# EEZ_DIB_DCP405_r2B8.net
KiCad netlist of a schematic drawn in EAGLE
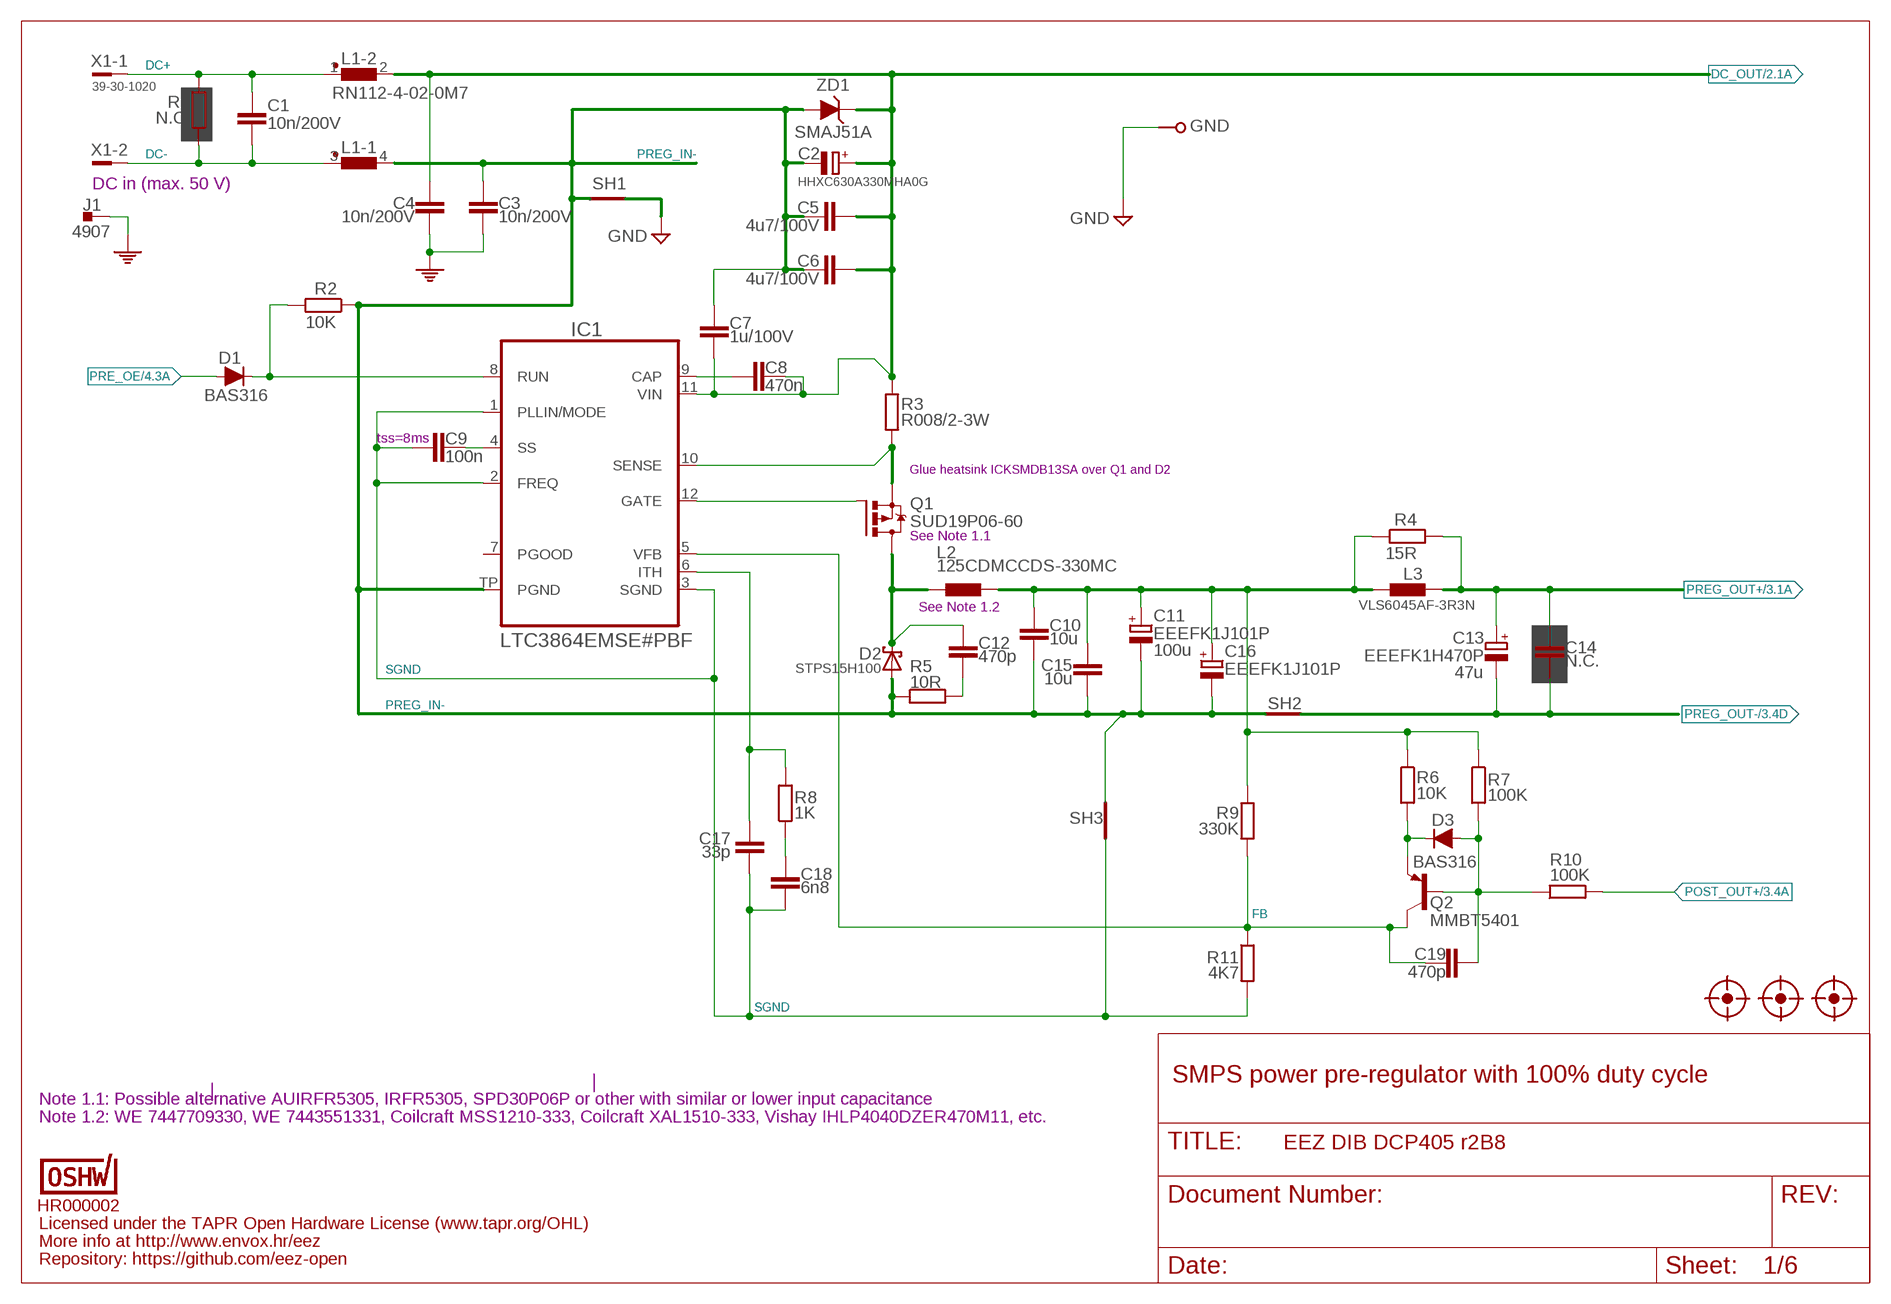
[diagram p0: schematic, sheet 1]
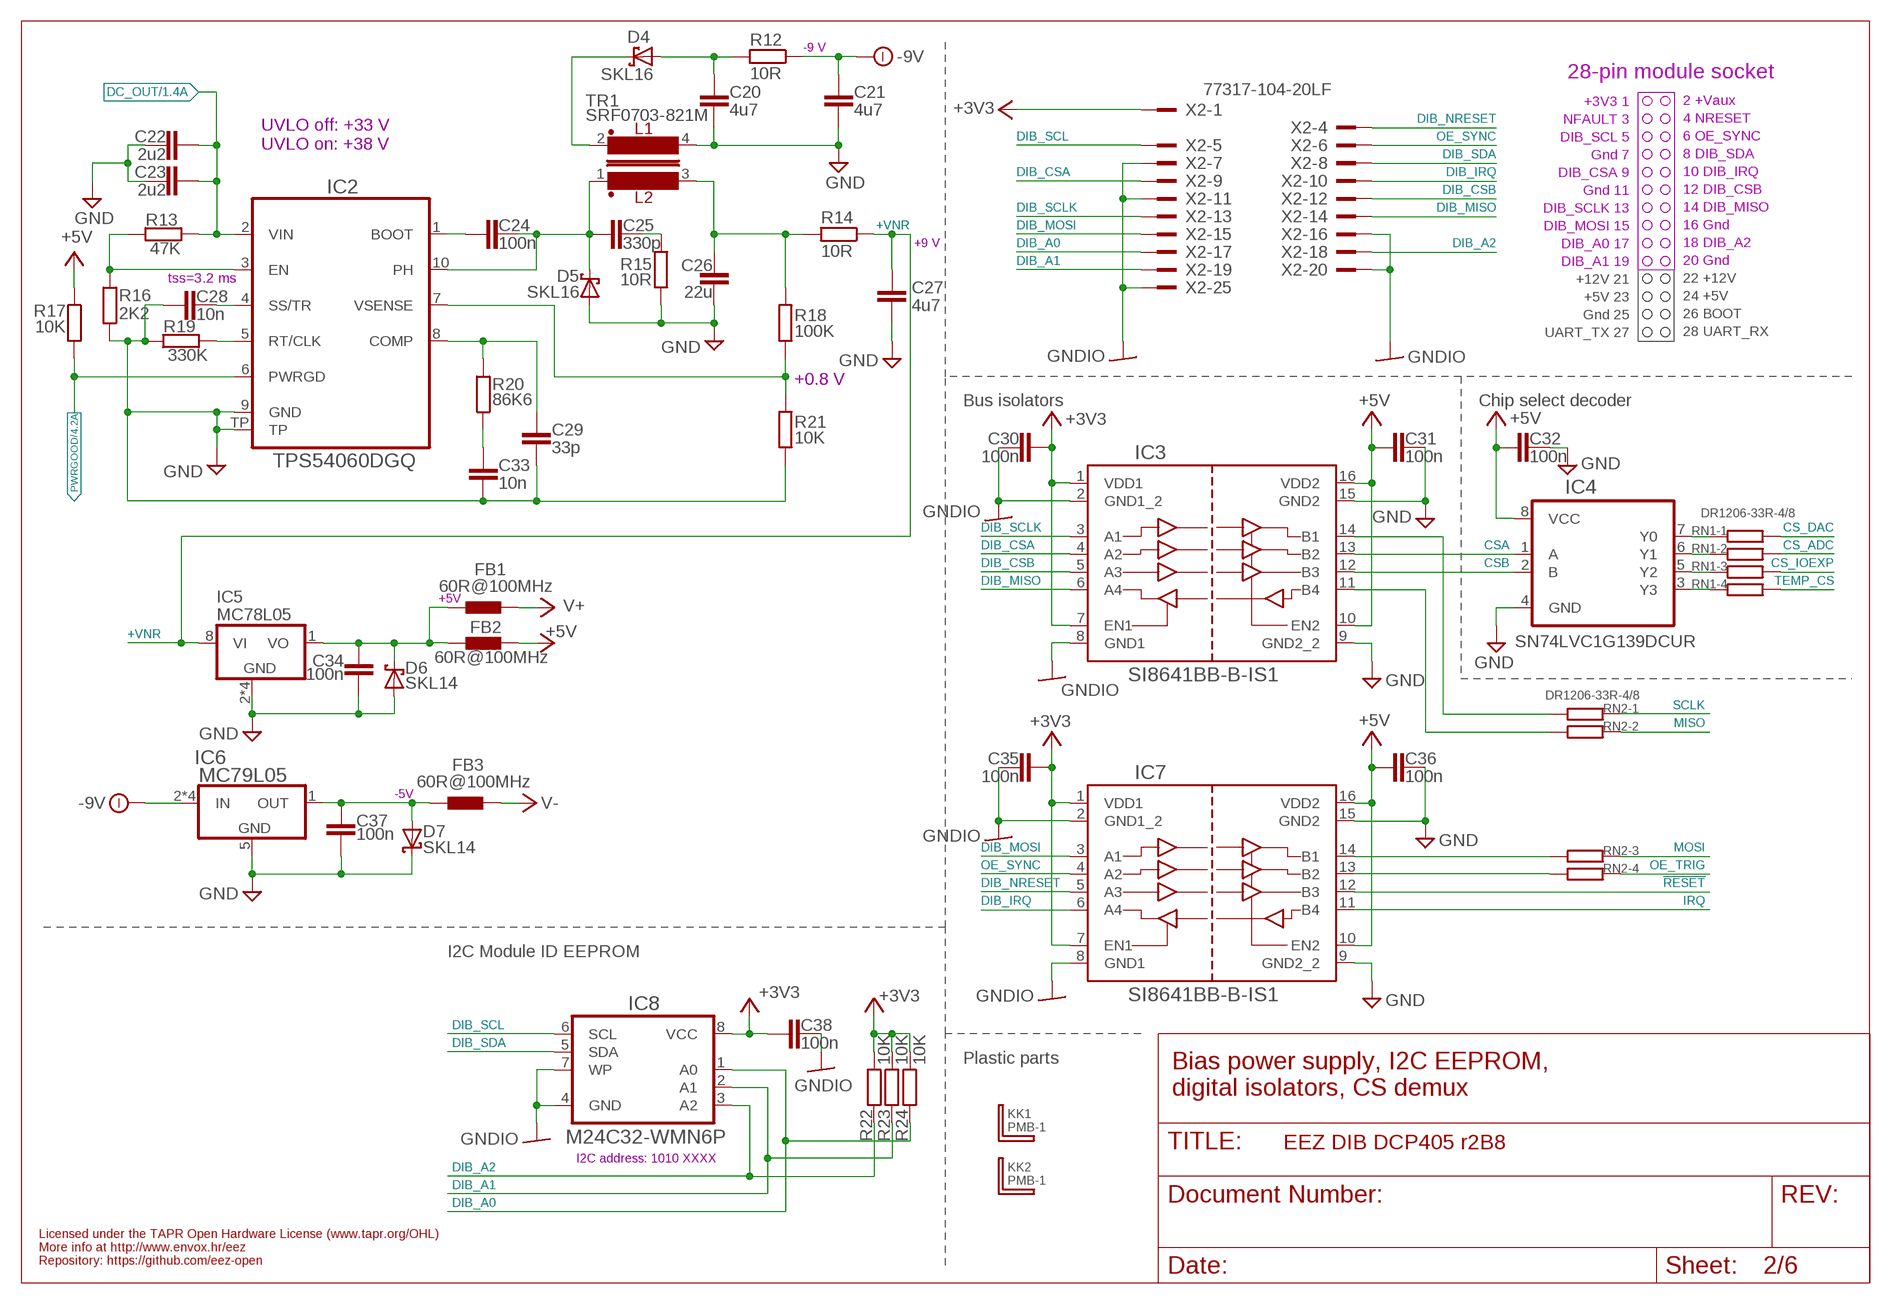
[diagram p1: schematic, sheet 2]
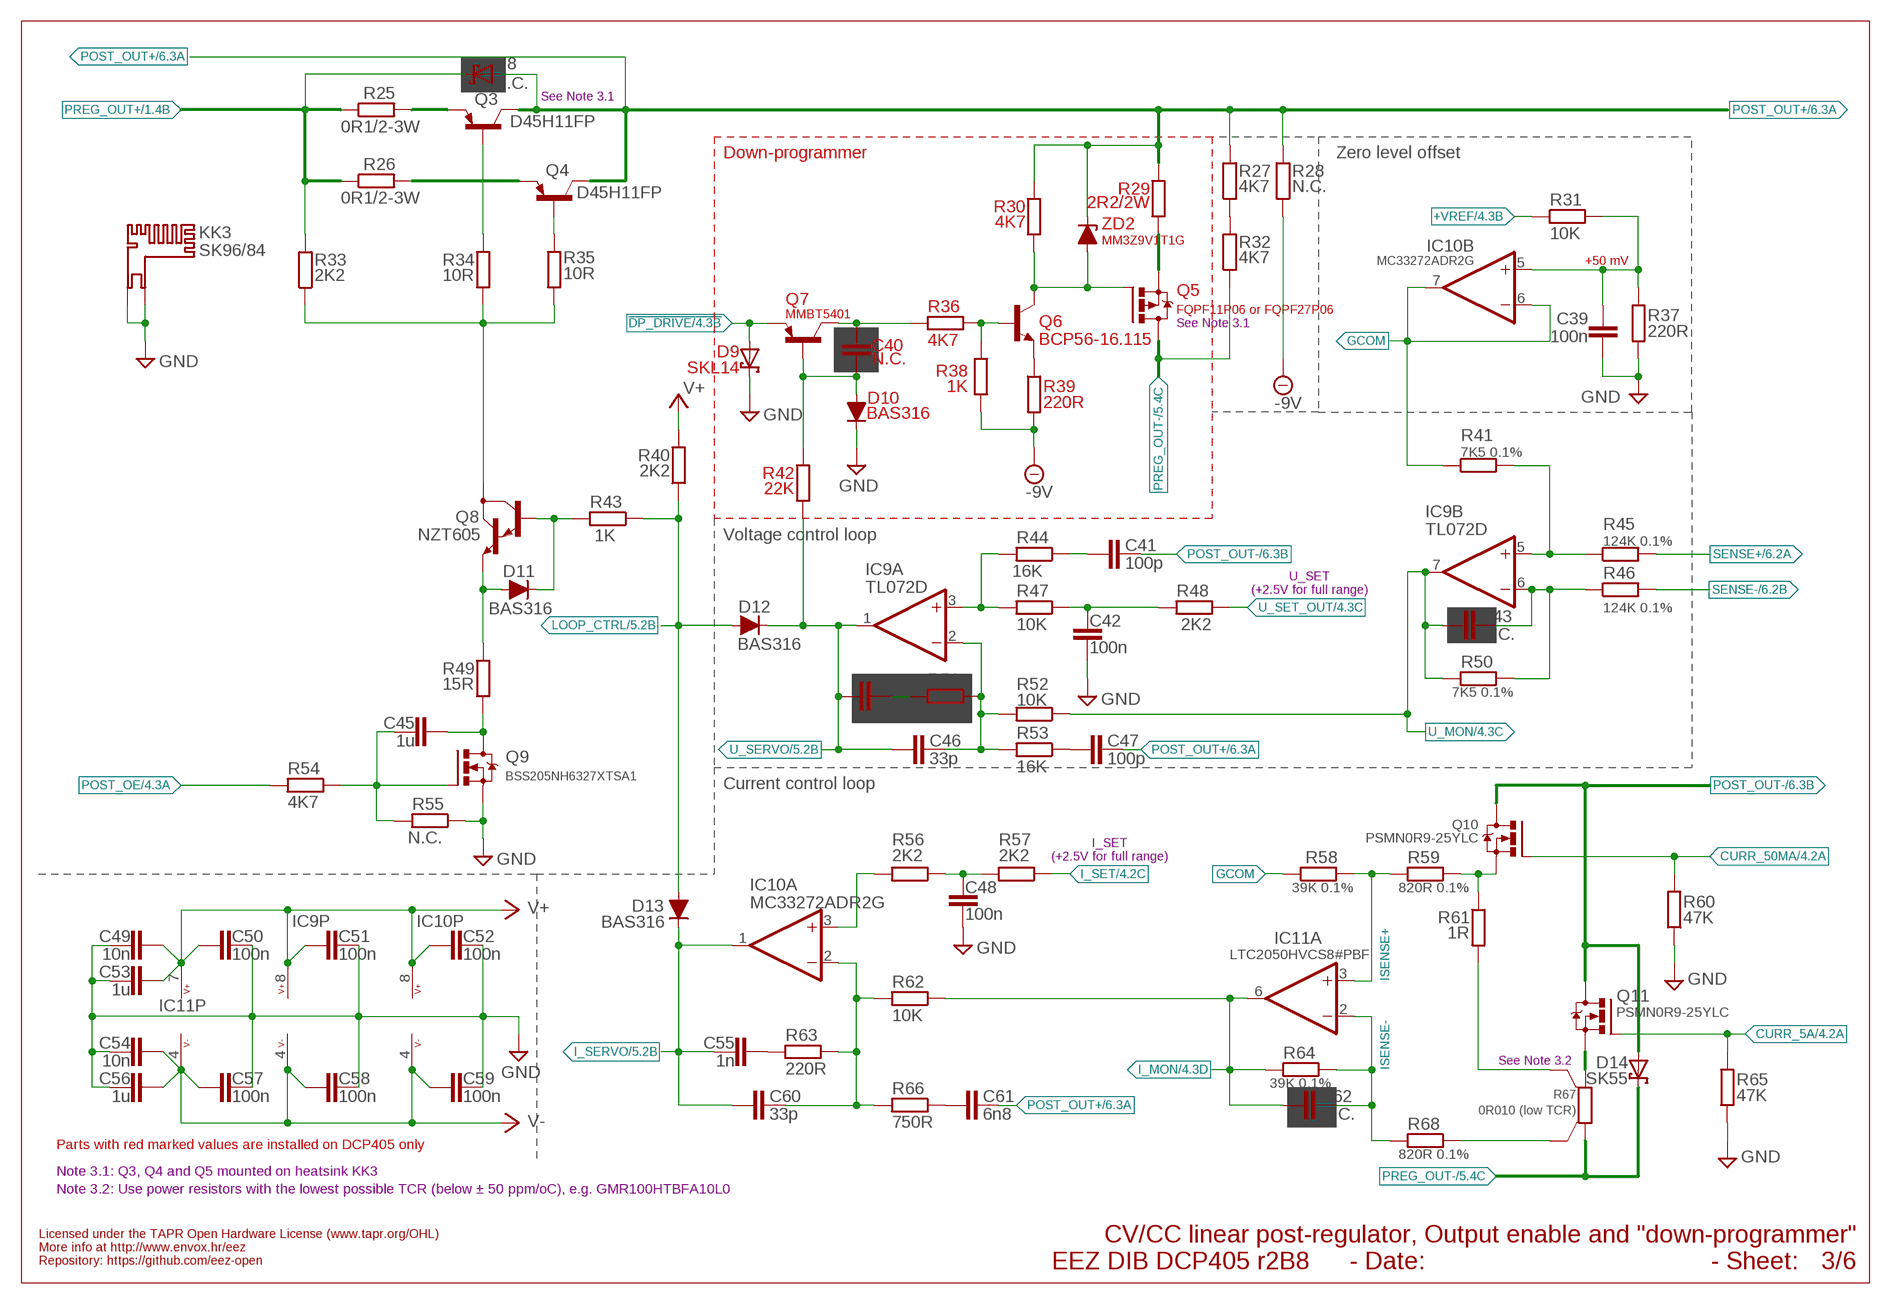
[diagram p2: schematic, sheet 3]
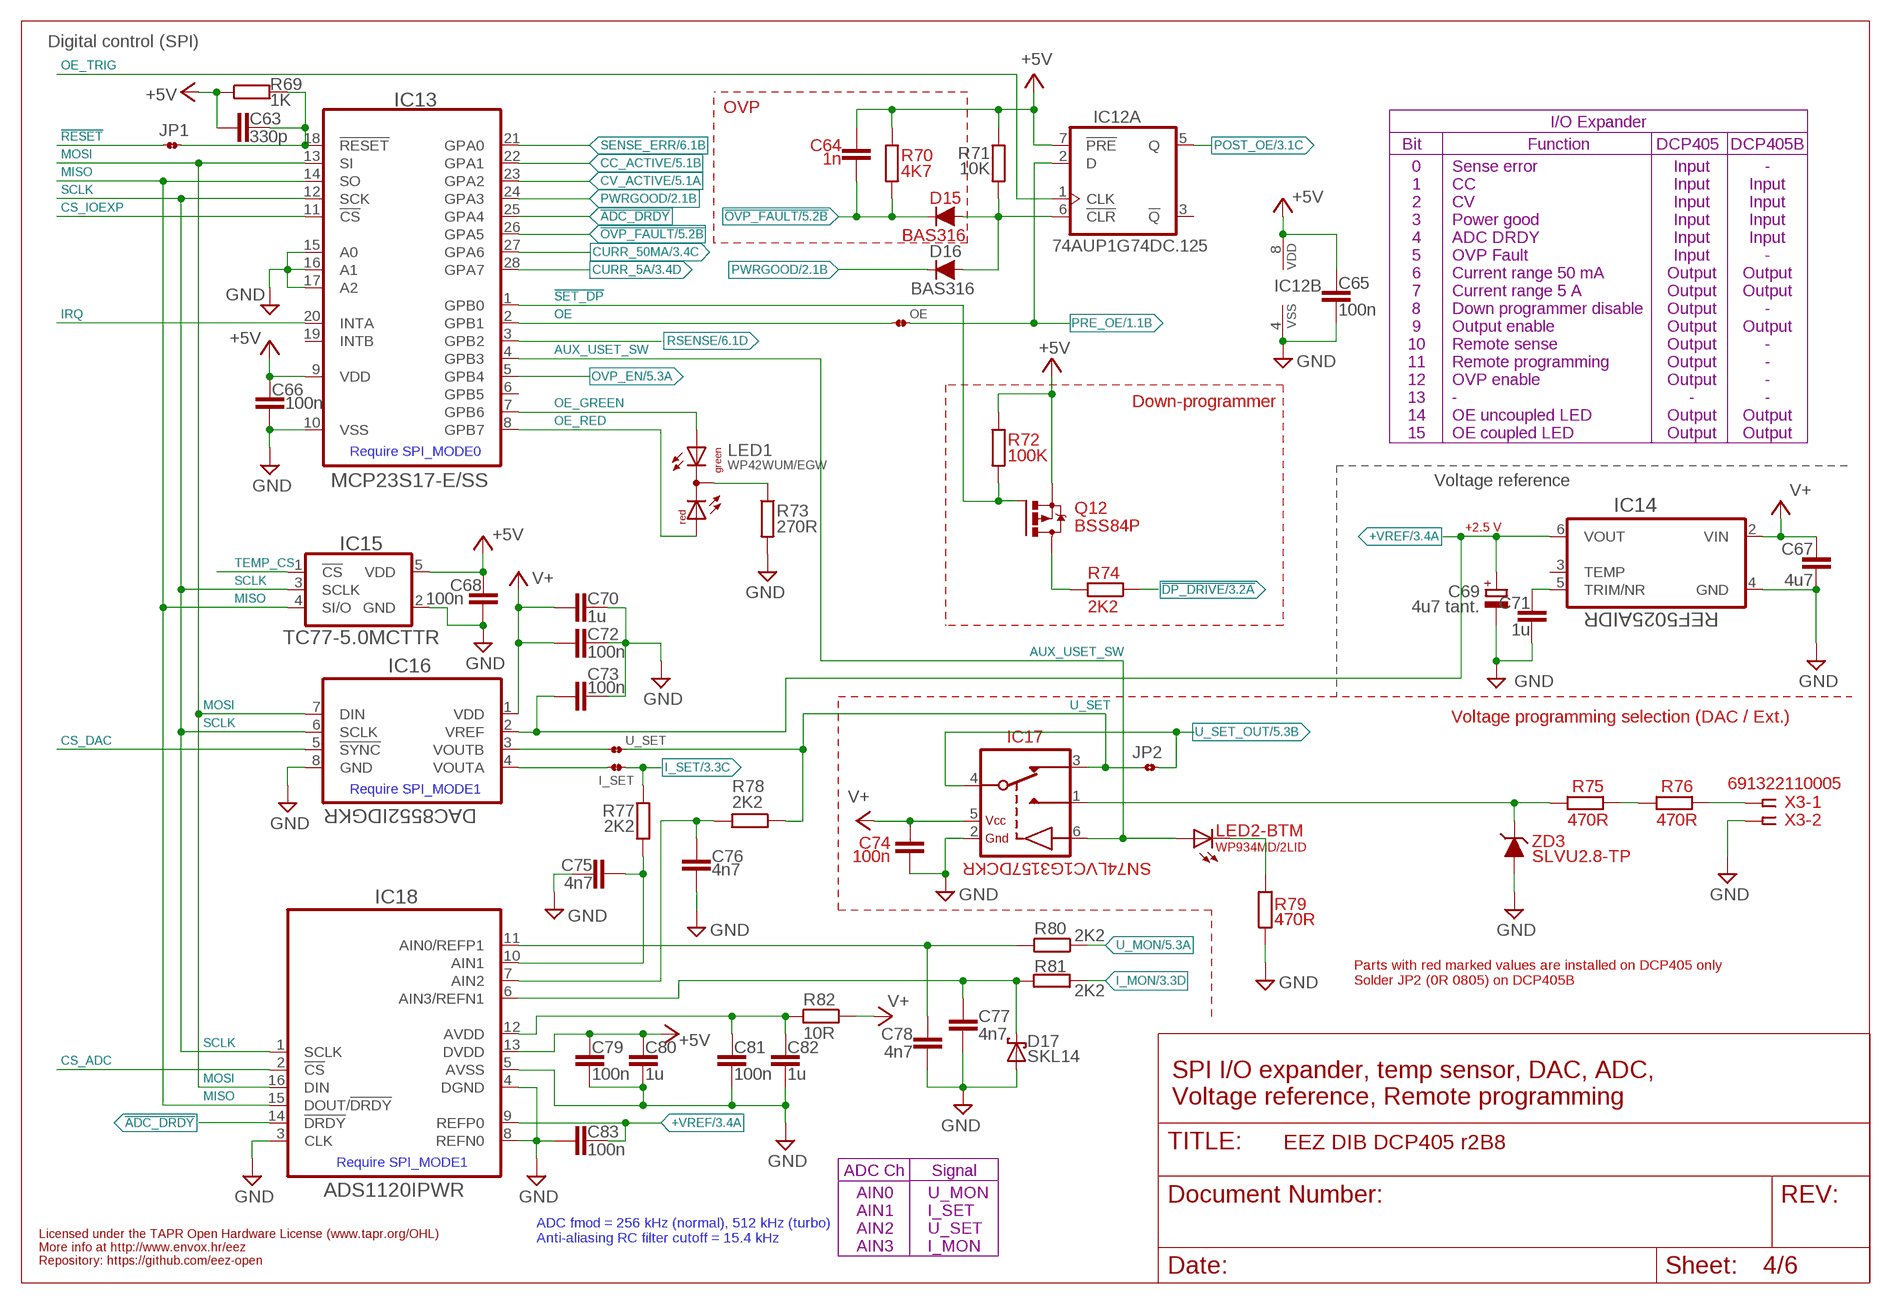
[diagram p3: schematic, sheet 4]
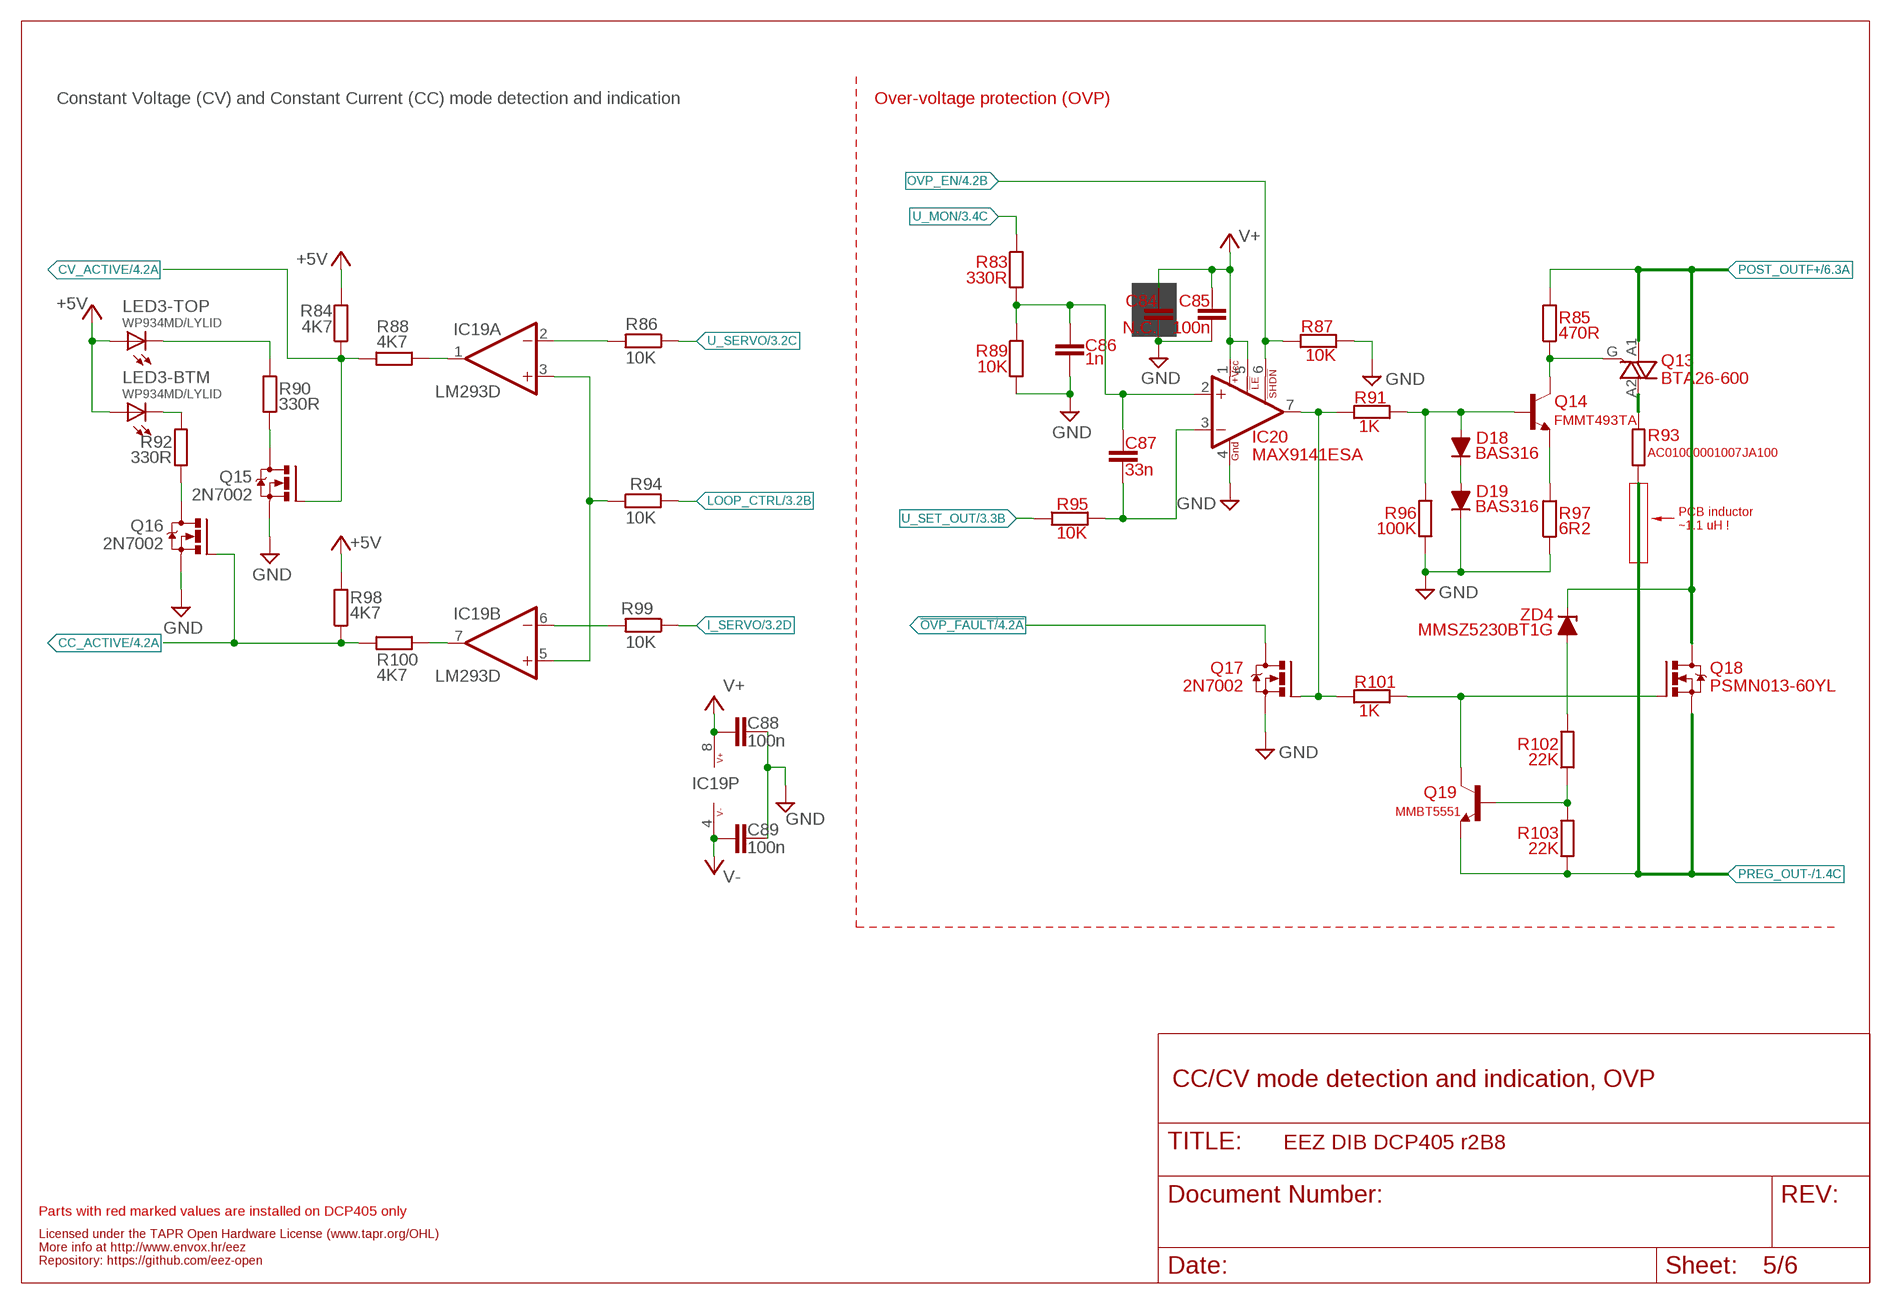
[diagram p4: schematic, sheet 5]
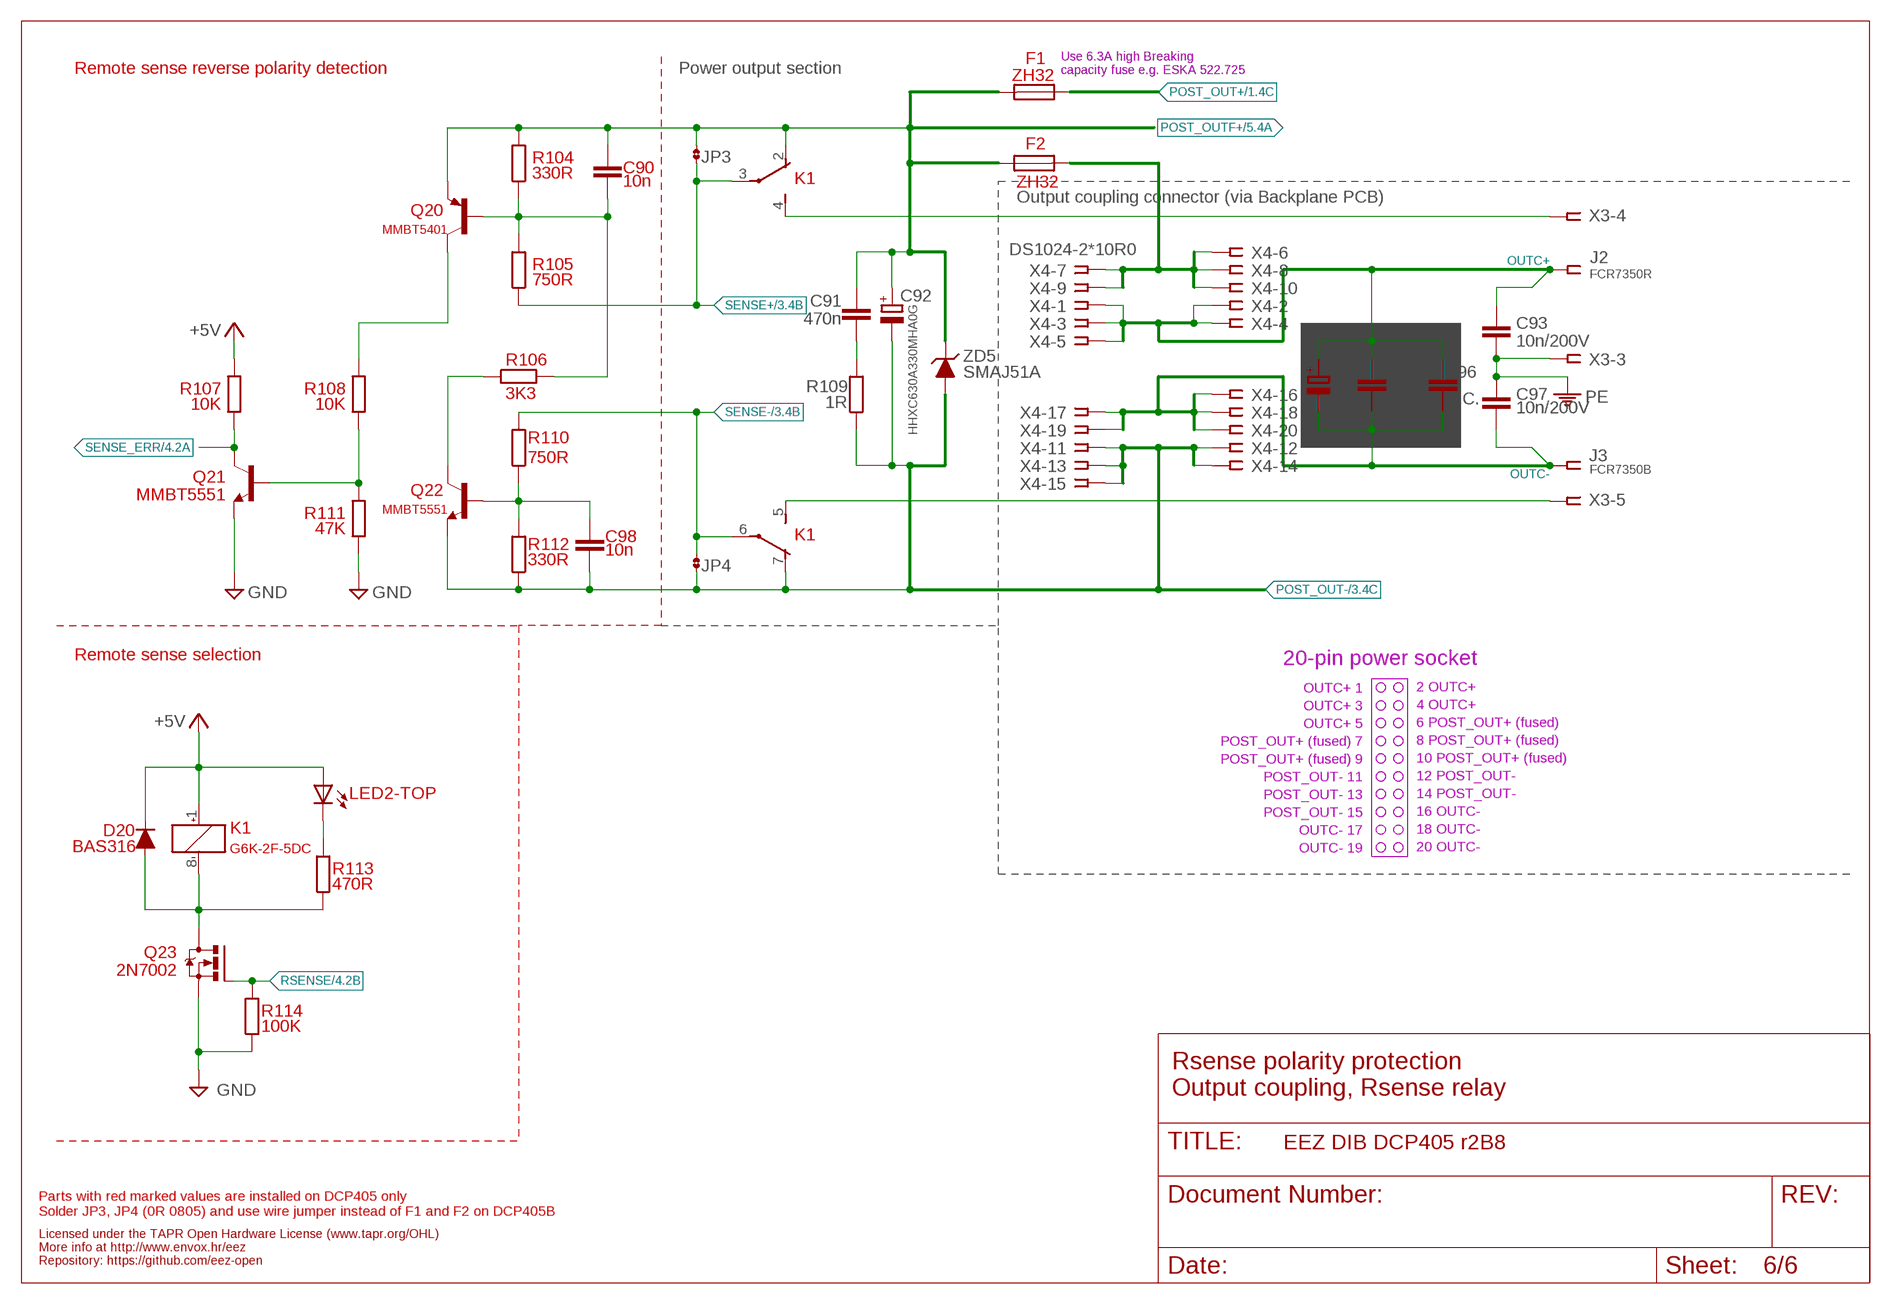
[diagram p5: schematic, sheet 6]

(export (version "E")
  (design (tool "Eeschema 10.0.6"))
  (components
    (comp (ref "C1")
      (value "10n/200V")
      (footprint "eagle-import:C1206")
      (libsource (lib "eagle-import") (part "C-EUC1206"))
    )
    (comp (ref "C2")
      (value "HHXC630A330MHA0G")
      (footprint "eagle-import:CAPAE830X1050N")
      (libsource (lib "eagle-import") (part "ECAPSMD8.3MM/HA0"))
    )
    (comp (ref "C3")
      (value "10n/200V")
      (footprint "eagle-import:C1206")
      (libsource (lib "eagle-import") (part "C-EUC1206"))
    )
    (comp (ref "C4")
      (value "10n/200V")
      (footprint "eagle-import:C1206")
      (libsource (lib "eagle-import") (part "C-EUC1206"))
    )
    (comp (ref "C5")
      (value "4u7/100V")
      (footprint "eagle-import:C1210")
      (libsource (lib "eagle-import") (part "C-EUC1210"))
    )
    (comp (ref "C6")
      (value "4u7/100V")
      (footprint "eagle-import:C1210")
      (libsource (lib "eagle-import") (part "C-EUC1210"))
    )
    (comp (ref "C7")
      (value "1u/100V")
      (footprint "eagle-import:C1206")
      (libsource (lib "eagle-import") (part "C-EUC1206"))
    )
    (comp (ref "C8")
      (value "470n")
      (footprint "eagle-import:C0805")
      (libsource (lib "eagle-import") (part "C-EUC0805"))
    )
    (comp (ref "C9")
      (value "100n")
      (footprint "eagle-import:C0603")
      (libsource (lib "eagle-import") (part "C-EUC0603"))
    )
    (comp (ref "C10")
      (value "10u")
      (footprint "eagle-import:C1210")
      (libsource (lib "eagle-import") (part "C-EUC1210"))
    )
    (comp (ref "C11")
      (value "EEEFK1J101P")
      (footprint "eagle-import:CAPAE1030X1050N")
      (libsource (lib "eagle-import") (part "ECAP10X10"))
    )
    (comp (ref "C12")
      (value "470p")
      (footprint "eagle-import:C0805")
      (libsource (lib "eagle-import") (part "C-EUC0805"))
    )
    (comp (ref "C13")
      (value "EEEFK1H470P")
      (footprint "eagle-import:CAPAE830X1050N")
      (libsource (lib "eagle-import") (part "ECAPSMD8.3MM/HA0"))
    )
    (comp (ref "C14")
      (value "N.C.")
      (footprint "eagle-import:C0805")
      (libsource (lib "eagle-import") (part "C-EUC0805"))
    )
    (comp (ref "C15")
      (value "10u")
      (footprint "eagle-import:C1210")
      (libsource (lib "eagle-import") (part "C-EUC1210"))
    )
    (comp (ref "C16")
      (value "EEEFK1J101P")
      (footprint "eagle-import:CAPAE1030X1050N")
      (libsource (lib "eagle-import") (part "ECAP10X10"))
    )
    (comp (ref "C17")
      (value "33p")
      (footprint "eagle-import:C0805")
      (libsource (lib "eagle-import") (part "C-EUC0805"))
    )
    (comp (ref "C18")
      (value "6n8")
      (footprint "eagle-import:C0805")
      (libsource (lib "eagle-import") (part "C-EUC0805"))
    )
    (comp (ref "C19")
      (value "470p")
      (footprint "eagle-import:C0805")
      (libsource (lib "eagle-import") (part "C-EUC0805"))
    )
    (comp (ref "D1")
      (value "BAS316")
      (footprint "eagle-import:SOD323-R")
      (libsource (lib "eagle-import") (part "DIODESOD323R"))
    )
    (comp (ref "D2")
      (value "STPS15H100")
      (footprint "eagle-import:TO252-L")
      (libsource (lib "eagle-import") (part "SCHOTTKY-DUAL_A_L"))
    )
    (comp (ref "D3")
      (value "BAS316")
      (footprint "eagle-import:SOD323-R")
      (libsource (lib "eagle-import") (part "DIODESOD323R"))
    )
    (comp (ref "FM1")
      (value "FIDUCIAL_2")
      (footprint "eagle-import:FIDUCIAL_DUAL")
      (libsource (lib "eagle-import") (part "FIDUCIAL_2"))
    )
    (comp (ref "FM2")
      (value "FIDUCIAL_2")
      (footprint "eagle-import:FIDUCIAL_DUAL")
      (libsource (lib "eagle-import") (part "FIDUCIAL_2"))
    )
    (comp (ref "FM3")
      (value "FIDUCIAL_2")
      (footprint "eagle-import:FIDUCIAL_DUAL")
      (libsource (lib "eagle-import") (part "FIDUCIAL_2"))
    )
    (comp (ref "GND")
      (value "PCB_TEST_TABSHIELD")
      (footprint "eagle-import:PCB_SHIELD_TAB")
      (libsource (lib "eagle-import") (part "PCB_TEST_TABSHIELD"))
    )
    (comp (ref "IC1")
      (value "LTC3864EMSE#PBF")
      (footprint "eagle-import:LTC_05-08-1666")
      (libsource (lib "eagle-import") (part "LTC3864"))
    )
    (comp (ref "J1")
      (value "4907")
      (footprint "eagle-import:PCB_TAB-4907")
      (libsource (lib "eagle-import") (part "PCB_TAB-4907"))
    )
    (comp (ref "L1")
      (value "RN112-4-02-0M7")
      (footprint "eagle-import:RN112")
      (libsource (lib "eagle-import") (part "RN112"))
    )
    (comp (ref "L2")
      (value "125CDMCCDS-330MC")
      (footprint "eagle-import:125CDMCC_DS")
      (libsource (lib "eagle-import") (part "125CDMCC/DS"))
    )
    (comp (ref "L3")
      (value "VLS6045AF-3R3N")
      (footprint "eagle-import:COILCRAFT_HPI0630")
      (libsource (lib "eagle-import") (part "COILCRAFT_HPI0630"))
    )
    (comp (ref "OSHWA")
      (value "HR000002")
      (footprint "eagle-import:CERT-SMALL-SILK")
      (libsource (lib "eagle-import") (part "OSHWA-CERT-SMALL"))
    )
    (comp (ref "Q1")
      (value "SUD19P06-60")
      (footprint "eagle-import:TO229P990X239-3N")
      (libsource (lib "eagle-import") (part "P-MOSFETDPAK"))
    )
    (comp (ref "Q2")
      (value "MMBT5401")
      (footprint "eagle-import:SOT23-BEC")
      (libsource (lib "eagle-import") (part "-PNP-SOT23-BECBC857B"))
    )
    (comp (ref "R1")
      (value "N.C.")
      (footprint "eagle-import:R2512")
      (libsource (lib "eagle-import") (part "R-EU_R2512"))
    )
    (comp (ref "R2")
      (value "10K")
      (footprint "eagle-import:R0805")
      (libsource (lib "eagle-import") (part "R-EU_R0805"))
    )
    (comp (ref "R3")
      (value "R008/2-3W")
      (footprint "eagle-import:R2512")
      (libsource (lib "eagle-import") (part "R-EU_R2512"))
    )
    (comp (ref "R4")
      (value "15R")
      (footprint "eagle-import:R2010")
      (libsource (lib "eagle-import") (part "R-EU_R2010"))
    )
    (comp (ref "R5")
      (value "10R")
      (footprint "eagle-import:R1206")
      (libsource (lib "eagle-import") (part "R-EU_R1206"))
    )
    (comp (ref "R6")
      (value "10K")
      (footprint "eagle-import:R0805")
      (libsource (lib "eagle-import") (part "R-EU_R0805"))
    )
    (comp (ref "R7")
      (value "100K")
      (footprint "eagle-import:R0805")
      (libsource (lib "eagle-import") (part "R-EU_R0805"))
    )
    (comp (ref "R8")
      (value "1K")
      (footprint "eagle-import:R0805")
      (libsource (lib "eagle-import") (part "R-EU_R0805"))
    )
    (comp (ref "R9")
      (value "330K")
      (footprint "eagle-import:R0805")
      (libsource (lib "eagle-import") (part "R-EU_R0805"))
    )
    (comp (ref "R10")
      (value "100K")
      (footprint "eagle-import:R0805")
      (libsource (lib "eagle-import") (part "R-EU_R0805"))
    )
    (comp (ref "R11")
      (value "4K7")
      (footprint "eagle-import:R0805")
      (libsource (lib "eagle-import") (part "R-EU_R0805"))
    )
    (comp (ref "SH1")
      (value "SHORTNOHOLE")
      (footprint "eagle-import:SHORT_NOHOLE")
      (libsource (lib "eagle-import") (part "SHORTNOHOLE"))
    )
    (comp (ref "SH2")
      (value "Pgnd to Pout- short")
      (footprint "eagle-import:SHORT_NOHOLE")
      (libsource (lib "eagle-import") (part "SHORTNOHOLE"))
    )
    (comp (ref "SH3")
      (value "Sgnd to Pgnd short")
      (footprint "eagle-import:SHORT_NOHOLE")
      (libsource (lib "eagle-import") (part "SHORTNOHOLE"))
    )
    (comp (ref "X1")
      (value "39-30-1020")
      (footprint "eagle-import:MINIFIT_39301020")
      (libsource (lib "eagle-import") (part "MINIFIT_39301020"))
    )
    (comp (ref "ZD1")
      (value "SMAJ51A")
      (footprint "eagle-import:DO214AA")
      (libsource (lib "eagle-import") (part "P6SMB68A"))
    )
    (comp (ref "C63")
      (value "330p")
      (footprint "eagle-import:C0805")
      (libsource (lib "eagle-import") (part "C-EUC0805"))
    )
    (comp (ref "C64")
      (value "1n")
      (footprint "eagle-import:C0805")
      (libsource (lib "eagle-import") (part "C-EUC0805"))
    )
    (comp (ref "C65")
      (value "100n")
      (footprint "eagle-import:C0603")
      (libsource (lib "eagle-import") (part "C-EUC0603"))
    )
    (comp (ref "C66")
      (value "100n")
      (footprint "eagle-import:C0603")
      (libsource (lib "eagle-import") (part "C-EUC0603"))
    )
    (comp (ref "C67")
      (value "4u7")
      (footprint "eagle-import:C1206")
      (libsource (lib "eagle-import") (part "C-EUC1206"))
    )
    (comp (ref "C68")
      (value "100n")
      (footprint "eagle-import:C0603")
      (libsource (lib "eagle-import") (part "C-EUC0603"))
    )
    (comp (ref "C69")
      (value "4u7 tant.")
      (footprint "eagle-import:EC1206")
      (libsource (lib "eagle-import") (part "ECAP1206"))
    )
    (comp (ref "C70")
      (value "1u")
      (footprint "eagle-import:C0805")
      (libsource (lib "eagle-import") (part "C-EUC0805"))
    )
    (comp (ref "C71")
      (value "1u")
      (footprint "eagle-import:C0805")
      (libsource (lib "eagle-import") (part "C-EUC0805"))
    )
    (comp (ref "C72")
      (value "100n")
      (footprint "eagle-import:C0603")
      (libsource (lib "eagle-import") (part "C-EUC0603"))
    )
    (comp (ref "C73")
      (value "100n")
      (footprint "eagle-import:C0603")
      (libsource (lib "eagle-import") (part "C-EUC0603"))
    )
    (comp (ref "C74")
      (value "100n")
      (footprint "eagle-import:C0603")
      (libsource (lib "eagle-import") (part "C-EUC0603"))
    )
    (comp (ref "C75")
      (value "4n7")
      (footprint "eagle-import:C0805")
      (libsource (lib "eagle-import") (part "C-EUC0805"))
    )
    (comp (ref "C76")
      (value "4n7")
      (footprint "eagle-import:C0805")
      (libsource (lib "eagle-import") (part "C-EUC0805"))
    )
    (comp (ref "C77")
      (value "4n7")
      (footprint "eagle-import:C0805")
      (libsource (lib "eagle-import") (part "C-EUC0805"))
    )
    (comp (ref "C78")
      (value "4n7")
      (footprint "eagle-import:C0805")
      (libsource (lib "eagle-import") (part "C-EUC0805"))
    )
    (comp (ref "C79")
      (value "100n")
      (footprint "eagle-import:C0603")
      (libsource (lib "eagle-import") (part "C-EUC0603"))
    )
    (comp (ref "C80")
      (value "1u")
      (footprint "eagle-import:C0805")
      (libsource (lib "eagle-import") (part "C-EUC0805"))
    )
    (comp (ref "C81")
      (value "100n")
      (footprint "eagle-import:C0603")
      (libsource (lib "eagle-import") (part "C-EUC0603"))
    )
    (comp (ref "C82")
      (value "1u")
      (footprint "eagle-import:C0805")
      (libsource (lib "eagle-import") (part "C-EUC0805"))
    )
    (comp (ref "C83")
      (value "100n")
      (footprint "eagle-import:C0603")
      (libsource (lib "eagle-import") (part "C-EUC0603"))
    )
    (comp (ref "D15")
      (value "BAS316")
      (footprint "eagle-import:SOD323-R")
      (libsource (lib "eagle-import") (part "DIODESOD323R"))
    )
    (comp (ref "D16")
      (value "BAS316")
      (footprint "eagle-import:SOD323-R")
      (libsource (lib "eagle-import") (part "DIODESOD323R"))
    )
    (comp (ref "D17")
      (value "SKL14")
      (footprint "eagle-import:SOD123")
      (libsource (lib "eagle-import") (part "SCHOTTKYSOD123"))
    )
    (comp (ref "IC12")
      (value "74AUP1G74DC.125")
      (footprint "eagle-import:DCU8")
      (libsource (lib "eagle-import") (part "SN74LVC1G74DCTR-VSSOP"))
    )
    (comp (ref "IC13")
      (value "MCP23S17-E/SS")
      (footprint "eagle-import:SOP65P780X200-28N")
      (libsource (lib "eagle-import") (part "MCP23S17-E/SSSSOP"))
    )
    (comp (ref "IC14")
      (value "REF5025AIDR")
      (footprint "eagle-import:SOIC127P600X175-8N")
      (libsource (lib "eagle-import") (part "REF50XX"))
    )
    (comp (ref "IC15")
      (value "TC77-5.0MCTTR")
      (footprint "eagle-import:SOT23-5")
      (libsource (lib "eagle-import") (part "TC77"))
    )
    (comp (ref "IC16")
      (value "DAC8552IDGKR")
      (footprint "eagle-import:DGK8-M")
      (libsource (lib "eagle-import") (part "DAC8552_DGK_8M"))
    )
    (comp (ref "IC17")
      (value "SN74LVC1G3157DCKR")
      (footprint "eagle-import:SOT65P210X110-6N")
      (libsource (lib "eagle-import") (part "SN74LVC1G3157-DCK"))
    )
    (comp (ref "IC18")
      (value "ADS1120IPWR")
      (footprint "eagle-import:PW(R-PDSO-G16)")
      (libsource (lib "eagle-import") (part "ADS1120TSSOP-16"))
    )
    (comp (ref "I_SET")
      (value "JP2-NOCUT")
      (footprint "eagle-import:JP2-NOCUT")
      (libsource (lib "eagle-import") (part "JP2-NOCUT"))
    )
    (comp (ref "JP1")
      (value "JP2-NOCUT")
      (footprint "eagle-import:JP2-NOCUT")
      (libsource (lib "eagle-import") (part "JP2-NOCUT"))
    )
    (comp (ref "JP2")
      (value "JP2-CUT-0805")
      (footprint "eagle-import:R_0805")
      (libsource (lib "eagle-import") (part "JP2-CUT-0805"))
    )
    (comp (ref "LED1")
      (value "WP42WUM/EGW")
      (footprint "eagle-import:L-42WUM-1EGWT")
      (libsource (lib "eagle-import") (part "LED_L-42WUM/1EGWT"))
    )
    (comp (ref "LED2")
      (value "WP934MD/2LID")
      (footprint "eagle-import:WP934MD")
      (libsource (lib "eagle-import") (part "WP934MD/2LID"))
    )
    (comp (ref "OE")
      (value "JP2-NOCUT")
      (footprint "eagle-import:JP2-NOCUT")
      (libsource (lib "eagle-import") (part "JP2-NOCUT"))
    )
    (comp (ref "Q12")
      (value "BSS84P")
      (footprint "eagle-import:SOT95P237X112-3N")
      (fields (field (name "MPN") "IRLML2246TRPBF"))
      (libsource (lib "eagle-import") (part "IRLML2246TRPBF"))
    )
    (comp (ref "R69")
      (value "1K")
      (footprint "eagle-import:R0805")
      (libsource (lib "eagle-import") (part "R-EU_R0805"))
    )
    (comp (ref "R70")
      (value "4K7")
      (footprint "eagle-import:R0805")
      (libsource (lib "eagle-import") (part "R-EU_R0805"))
    )
    (comp (ref "R71")
      (value "10K")
      (footprint "eagle-import:R0805")
      (libsource (lib "eagle-import") (part "R-EU_R0805"))
    )
    (comp (ref "R72")
      (value "100K")
      (footprint "eagle-import:R0805")
      (libsource (lib "eagle-import") (part "R-EU_R0805"))
    )
    (comp (ref "R73")
      (value "270R")
      (footprint "eagle-import:R0805")
      (libsource (lib "eagle-import") (part "R-EU_R0805"))
    )
    (comp (ref "R74")
      (value "2K2")
      (footprint "eagle-import:R0805")
      (libsource (lib "eagle-import") (part "R-EU_R0805"))
    )
    (comp (ref "R75")
      (value "470R")
      (footprint "eagle-import:R0805")
      (libsource (lib "eagle-import") (part "R-EU_R0805"))
    )
    (comp (ref "R76")
      (value "470R")
      (footprint "eagle-import:R0805")
      (libsource (lib "eagle-import") (part "R-EU_R0805"))
    )
    (comp (ref "R77")
      (value "2K2")
      (footprint "eagle-import:R0805")
      (libsource (lib "eagle-import") (part "R-EU_R0805"))
    )
    (comp (ref "R78")
      (value "2K2")
      (footprint "eagle-import:R0805")
      (libsource (lib "eagle-import") (part "R-EU_R0805"))
    )
    (comp (ref "R79")
      (value "470R")
      (footprint "eagle-import:R0805")
      (libsource (lib "eagle-import") (part "R-EU_R0805"))
    )
    (comp (ref "R80")
      (value "2K2")
      (footprint "eagle-import:R0805")
      (libsource (lib "eagle-import") (part "R-EU_R0805"))
    )
    (comp (ref "R81")
      (value "2K2")
      (footprint "eagle-import:R0805")
      (libsource (lib "eagle-import") (part "R-EU_R0805"))
    )
    (comp (ref "R82")
      (value "10R")
      (footprint "eagle-import:R1206")
      (libsource (lib "eagle-import") (part "R-EU_R1206"))
    )
    (comp (ref "U_SET")
      (value "JP2-NOCUT")
      (footprint "eagle-import:JP2-NOCUT")
      (libsource (lib "eagle-import") (part "JP2-NOCUT"))
    )
    (comp (ref "X3")
      (value "691322110005")
      (footprint "eagle-import:MC1,5_5-G-3,5")
      (libsource (lib "eagle-import") (part "MC1,5/5-G-3,5"))
    )
    (comp (ref "ZD3")
      (value "SLVU2.8-TP")
      (footprint "eagle-import:SOT23")
      (libsource (lib "eagle-import") (part "SLVU2.8"))
    )
    (comp (ref "C84")
      (value "N.C.")
      (footprint "eagle-import:C0805")
      (libsource (lib "eagle-import") (part "C-EUC0805"))
    )
    (comp (ref "C85")
      (value "100n")
      (footprint "eagle-import:C0603")
      (libsource (lib "eagle-import") (part "C-EUC0603"))
    )
    (comp (ref "C86")
      (value "1n")
      (footprint "eagle-import:C0805")
      (libsource (lib "eagle-import") (part "C-EUC0805"))
    )
    (comp (ref "C87")
      (value "33n")
      (footprint "eagle-import:C0805")
      (libsource (lib "eagle-import") (part "C-EUC0805"))
    )
    (comp (ref "C88")
      (value "100n")
      (footprint "eagle-import:C0603")
      (libsource (lib "eagle-import") (part "C-EUC0603"))
    )
    (comp (ref "C89")
      (value "100n")
      (footprint "eagle-import:C0603")
      (libsource (lib "eagle-import") (part "C-EUC0603"))
    )
    (comp (ref "D18")
      (value "BAS316")
      (footprint "eagle-import:SOD323-R")
      (libsource (lib "eagle-import") (part "DIODESOD323R"))
    )
    (comp (ref "D19")
      (value "BAS316")
      (footprint "eagle-import:SOD323-R")
      (libsource (lib "eagle-import") (part "DIODESOD323R"))
    )
    (comp (ref "IC19")
      (value "LM293D")
      (footprint "eagle-import:SOIC127P600X173-8N")
      (libsource (lib "eagle-import") (part "LM293D"))
    )
    (comp (ref "IC20")
      (value "MAX9141ESA")
      (footprint "eagle-import:SOIC127P600X173-8N")
      (libsource (lib "eagle-import") (part "MAX9141ESA"))
    )
    (comp (ref "LED3")
      (value "WP934MD/LYLID")
      (footprint "eagle-import:WP934MD")
      (libsource (lib "eagle-import") (part "WP934MD/LYLID"))
    )
    (comp (ref "Q13")
      (value "BTA26-600")
      (footprint "eagle-import:TOP3_TRIAC_NOHOLE")
      (libsource (lib "eagle-import") (part "BTA41-2"))
    )
    (comp (ref "Q14")
      (value "FMMT493TA")
      (footprint "eagle-import:SOT23-BEC")
      (libsource (lib "eagle-import") (part "-NPN-SOT23-BECMMBT5551LT1"))
    )
    (comp (ref "Q15")
      (value "2N7002")
      (footprint "eagle-import:SOT103P240X110-3N")
      (fields (field (name "MPN") "2N7002-7-F"))
      (libsource (lib "eagle-import") (part "2N7002"))
    )
    (comp (ref "Q16")
      (value "2N7002")
      (footprint "eagle-import:SOT103P240X110-3N")
      (fields (field (name "MPN") "2N7002-7-F"))
      (libsource (lib "eagle-import") (part "2N7002"))
    )
    (comp (ref "Q17")
      (value "2N7002")
      (footprint "eagle-import:SOT103P240X110-3N")
      (fields
        (field (name "MPN") "2N7002-7-F")
        (field (name "MPN_1") "2N7002-7-F")
        (field (name "OC_FARNELL") "1713823")
        (field (name "OC_NEWARK") "25R5679")
        (field (name "PACKAGE") "SOT-23-3")
        (field (name "SUPPLIER") "DIODES INC.")
      )
      (libsource (lib "eagle-import") (part "2N7002"))
    )
    (comp (ref "Q18")
      (value "PSMN013-60YL")
      (footprint "eagle-import:SOT669")
      (libsource (lib "eagle-import") (part "N-MOSFETLFPAK"))
    )
    (comp (ref "Q19")
      (value "MMBT5551")
      (footprint "eagle-import:SOT23-BEC")
      (libsource (lib "eagle-import") (part "-NPN-SOT23-BECMMBT5551LT1"))
    )
    (comp (ref "R83")
      (value "330R")
      (footprint "eagle-import:R0805")
      (libsource (lib "eagle-import") (part "R-EU_R0805"))
    )
    (comp (ref "R84")
      (value "4K7")
      (footprint "eagle-import:R0805")
      (libsource (lib "eagle-import") (part "R-EU_R0805"))
    )
    (comp (ref "R85")
      (value "470R")
      (footprint "eagle-import:R0805")
      (libsource (lib "eagle-import") (part "R-EU_R0805"))
    )
    (comp (ref "R86")
      (value "10K")
      (footprint "eagle-import:R0805")
      (libsource (lib "eagle-import") (part "R-EU_R0805"))
    )
    (comp (ref "R87")
      (value "10K")
      (footprint "eagle-import:R0805")
      (libsource (lib "eagle-import") (part "R-EU_R0805"))
    )
    (comp (ref "R88")
      (value "4K7")
      (footprint "eagle-import:R0805")
      (libsource (lib "eagle-import") (part "R-EU_R0805"))
    )
    (comp (ref "R89")
      (value "10K")
      (footprint "eagle-import:R0805")
      (libsource (lib "eagle-import") (part "R-EU_R0805"))
    )
    (comp (ref "R90")
      (value "330R")
      (footprint "eagle-import:R0805")
      (libsource (lib "eagle-import") (part "R-EU_R0805"))
    )
    (comp (ref "R91")
      (value "1K")
      (footprint "eagle-import:R0805")
      (libsource (lib "eagle-import") (part "R-EU_R0805"))
    )
    (comp (ref "R92")
      (value "330R")
      (footprint "eagle-import:R0805")
      (libsource (lib "eagle-import") (part "R-EU_R0805"))
    )
    (comp (ref "R93")
      (value "AC01000001007JA100")
      (footprint "eagle-import:0411_15")
      (libsource (lib "eagle-import") (part "R-EU_0411/15"))
    )
    (comp (ref "R94")
      (value "10K")
      (footprint "eagle-import:R0805")
      (libsource (lib "eagle-import") (part "R-EU_R0805"))
    )
    (comp (ref "R95")
      (value "10K")
      (footprint "eagle-import:R0805")
      (libsource (lib "eagle-import") (part "R-EU_R0805"))
    )
    (comp (ref "R96")
      (value "100K")
      (footprint "eagle-import:R0805")
      (libsource (lib "eagle-import") (part "R-EU_R0805"))
    )
    (comp (ref "R97")
      (value "6R2")
      (footprint "eagle-import:R0805")
      (libsource (lib "eagle-import") (part "R-EU_R0805"))
    )
    (comp (ref "R98")
      (value "4K7")
      (footprint "eagle-import:R0805")
      (libsource (lib "eagle-import") (part "R-EU_R0805"))
    )
    (comp (ref "R99")
      (value "10K")
      (footprint "eagle-import:R0805")
      (libsource (lib "eagle-import") (part "R-EU_R0805"))
    )
    (comp (ref "R100")
      (value "4K7")
      (footprint "eagle-import:R0805")
      (libsource (lib "eagle-import") (part "R-EU_R0805"))
    )
    (comp (ref "R101")
      (value "1K")
      (footprint "eagle-import:R0805")
      (libsource (lib "eagle-import") (part "R-EU_R0805"))
    )
    (comp (ref "R102")
      (value "22K")
      (footprint "eagle-import:R0805")
      (libsource (lib "eagle-import") (part "R-EU_R0805"))
    )
    (comp (ref "R103")
      (value "22K")
      (footprint "eagle-import:R0805")
      (libsource (lib "eagle-import") (part "R-EU_R0805"))
    )
    (comp (ref "ZD4")
      (value "MMSZ5230BT1G")
      (footprint "eagle-import:SOD123")
      (libsource (lib "eagle-import") (part "ZENER-DIODESOD123"))
    )
    (comp (ref "C39")
      (value "100n")
      (footprint "eagle-import:C0603")
      (libsource (lib "eagle-import") (part "C-EUC0603"))
    )
    (comp (ref "C40")
      (value "N.C.")
      (footprint "eagle-import:C0805")
      (libsource (lib "eagle-import") (part "C-EUC0805"))
    )
    (comp (ref "C41")
      (value "100p")
      (footprint "eagle-import:C0805")
      (libsource (lib "eagle-import") (part "C-EUC0805"))
    )
    (comp (ref "C42")
      (value "100n")
      (footprint "eagle-import:C0603")
      (libsource (lib "eagle-import") (part "C-EUC0603"))
    )
    (comp (ref "C43")
      (value "N.C.")
      (footprint "eagle-import:C0805")
      (libsource (lib "eagle-import") (part "C-EUC0805"))
    )
    (comp (ref "C44")
      (value "N.C.")
      (footprint "eagle-import:C0805")
      (libsource (lib "eagle-import") (part "C-EUC0805"))
    )
    (comp (ref "C45")
      (value "1u")
      (footprint "eagle-import:C0805")
      (libsource (lib "eagle-import") (part "C-EUC0805"))
    )
    (comp (ref "C46")
      (value "33p")
      (footprint "eagle-import:C0805")
      (libsource (lib "eagle-import") (part "C-EUC0805"))
    )
    (comp (ref "C47")
      (value "100p")
      (footprint "eagle-import:C0805")
      (libsource (lib "eagle-import") (part "C-EUC0805"))
    )
    (comp (ref "C48")
      (value "100n")
      (footprint "eagle-import:C0603")
      (libsource (lib "eagle-import") (part "C-EUC0603"))
    )
    (comp (ref "C49")
      (value "10n")
      (footprint "eagle-import:C0805")
      (libsource (lib "eagle-import") (part "C-EUC0805"))
    )
    (comp (ref "C50")
      (value "100n")
      (footprint "eagle-import:C0603")
      (libsource (lib "eagle-import") (part "C-EUC0603"))
    )
    (comp (ref "C51")
      (value "100n")
      (footprint "eagle-import:C0603")
      (libsource (lib "eagle-import") (part "C-EUC0603"))
    )
    (comp (ref "C52")
      (value "100n")
      (footprint "eagle-import:C0603")
      (libsource (lib "eagle-import") (part "C-EUC0603"))
    )
    (comp (ref "C53")
      (value "1u")
      (footprint "eagle-import:C0805")
      (libsource (lib "eagle-import") (part "C-EUC0805"))
    )
    (comp (ref "C54")
      (value "10n")
      (footprint "eagle-import:C0805")
      (libsource (lib "eagle-import") (part "C-EUC0805"))
    )
    (comp (ref "C55")
      (value "1n")
      (footprint "eagle-import:C0805")
      (libsource (lib "eagle-import") (part "C-EUC0805"))
    )
    (comp (ref "C56")
      (value "1u")
      (footprint "eagle-import:C0805")
      (libsource (lib "eagle-import") (part "C-EUC0805"))
    )
    (comp (ref "C57")
      (value "100n")
      (footprint "eagle-import:C0603")
      (libsource (lib "eagle-import") (part "C-EUC0603"))
    )
    (comp (ref "C58")
      (value "100n")
      (footprint "eagle-import:C0603")
      (libsource (lib "eagle-import") (part "C-EUC0603"))
    )
    (comp (ref "C59")
      (value "100n")
      (footprint "eagle-import:C0603")
      (libsource (lib "eagle-import") (part "C-EUC0603"))
    )
    (comp (ref "C60")
      (value "33p")
      (footprint "eagle-import:C0805")
      (libsource (lib "eagle-import") (part "C-EUC0805"))
    )
    (comp (ref "C61")
      (value "6n8")
      (footprint "eagle-import:C0805")
      (libsource (lib "eagle-import") (part "C-EUC0805"))
    )
    (comp (ref "C62")
      (value "N.C.")
      (footprint "eagle-import:C0805")
      (libsource (lib "eagle-import") (part "C-EUC0805"))
    )
    (comp (ref "D8")
      (value "N.C.")
      (footprint "eagle-import:SOD123")
      (libsource (lib "eagle-import") (part "SCHOTTKYSOD123"))
    )
    (comp (ref "D9")
      (value "SKL14")
      (footprint "eagle-import:SOD123")
      (libsource (lib "eagle-import") (part "SCHOTTKYSOD123"))
    )
    (comp (ref "D10")
      (value "BAS316")
      (footprint "eagle-import:SOD323-R")
      (libsource (lib "eagle-import") (part "DIODESOD323R"))
    )
    (comp (ref "D11")
      (value "BAS316")
      (footprint "eagle-import:SOD323-R")
      (libsource (lib "eagle-import") (part "DIODESOD323R"))
    )
    (comp (ref "D12")
      (value "BAS316")
      (footprint "eagle-import:SOD323-R")
      (libsource (lib "eagle-import") (part "DIODESOD323R"))
    )
    (comp (ref "D13")
      (value "BAS316")
      (footprint "eagle-import:SOD323-R")
      (libsource (lib "eagle-import") (part "DIODESOD323R"))
    )
    (comp (ref "D14")
      (value "SK55")
      (footprint "eagle-import:SMB")
      (libsource (lib "eagle-import") (part "SCHOTTKYSMB"))
    )
    (comp (ref "IC9")
      (value "TL072D")
      (footprint "eagle-import:SOIC127P600X173-8N")
      (libsource (lib "eagle-import") (part "TL072SOIC8"))
    )
    (comp (ref "IC10")
      (value "MC33272ADR2G")
      (footprint "eagle-import:SOIC127P600X173-8N")
      (libsource (lib "eagle-import") (part "TL072SOIC8"))
    )
    (comp (ref "IC11")
      (value "LTC2050HVCS8#PBF")
      (footprint "eagle-import:SOIC127P600X173-8N")
      (libsource (lib "eagle-import") (part "OP27GSZSO8"))
    )
    (comp (ref "KK3")
      (value "SK96/84")
      (footprint "eagle-import:SK96_84")
      (libsource (lib "eagle-import") (part "SK96/84"))
    )
    (comp (ref "Q3")
      (value "D45H11FP")
      (footprint "eagle-import:TO220FP-V")
      (libsource (lib "eagle-import") (part "D45H11-FPV"))
    )
    (comp (ref "Q4")
      (value "D45H11FP")
      (footprint "eagle-import:TO220FP-V")
      (libsource (lib "eagle-import") (part "D45H11-FPV"))
    )
    (comp (ref "Q5")
      (value "FQPF11P06 or FQPF27P06")
      (footprint "eagle-import:TO220FP-V")
      (libsource (lib "eagle-import") (part "P-MOSFET-FPV"))
    )
    (comp (ref "Q6")
      (value "BCP56-16.115")
      (footprint "eagle-import:SOT230P700X180-4N")
      (libsource (lib "eagle-import") (part "BCP56"))
    )
    (comp (ref "Q7")
      (value "MMBT5401")
      (footprint "eagle-import:SOT23-BEC")
      (libsource (lib "eagle-import") (part "-PNP-SOT23-BECBC857B"))
    )
    (comp (ref "Q8")
      (value "NZT605")
      (footprint "eagle-import:SOT230P700X180-4N")
      (libsource (lib "eagle-import") (part "NZT605"))
    )
    (comp (ref "Q9")
      (value "BSS205NH6327XTSA1")
      (footprint "eagle-import:SOT103P240X110-3N")
      (fields
        (field (name "MPN") "2N7002-7-F")
        (field (name "MPN_1") "2N7002-7-F")
        (field (name "OC_FARNELL") "1713823")
        (field (name "OC_NEWARK") "25R5679")
        (field (name "PACKAGE") "SOT-23-3")
        (field (name "SUPPLIER") "DIODES INC.")
      )
      (libsource (lib "eagle-import") (part "2N7002"))
    )
    (comp (ref "Q10")
      (value "PSMN0R9-25YLC")
      (footprint "eagle-import:SOT669")
      (libsource (lib "eagle-import") (part "N-MOSFETLFPAK"))
    )
    (comp (ref "Q11")
      (value "PSMN0R9-25YLC")
      (footprint "eagle-import:SOT669")
      (libsource (lib "eagle-import") (part "N-MOSFETLFPAK"))
    )
    (comp (ref "R25")
      (value "0R1/2-3W")
      (footprint "eagle-import:R2512")
      (libsource (lib "eagle-import") (part "R-EU_R2512"))
    )
    (comp (ref "R26")
      (value "0R1/2-3W")
      (footprint "eagle-import:R2512")
      (libsource (lib "eagle-import") (part "R-EU_R2512"))
    )
    (comp (ref "R27")
      (value "4K7")
      (footprint "eagle-import:R0805")
      (libsource (lib "eagle-import") (part "R-EU_R0805"))
    )
    (comp (ref "R28")
      (value "N.C.")
      (footprint "eagle-import:R0805")
      (libsource (lib "eagle-import") (part "R-EU_R0805"))
    )
    (comp (ref "R29")
      (value "2R2/2W")
      (footprint "eagle-import:R2512")
      (libsource (lib "eagle-import") (part "R-EU_R2512"))
    )
    (comp (ref "R30")
      (value "4K7")
      (footprint "eagle-import:R0805")
      (libsource (lib "eagle-import") (part "R-EU_R0805"))
    )
    (comp (ref "R31")
      (value "10K")
      (footprint "eagle-import:R0805")
      (libsource (lib "eagle-import") (part "R-EU_R0805"))
    )
    (comp (ref "R32")
      (value "4K7")
      (footprint "eagle-import:R0805")
      (libsource (lib "eagle-import") (part "R-EU_R0805"))
    )
    (comp (ref "R33")
      (value "2K2")
      (footprint "eagle-import:R0805")
      (libsource (lib "eagle-import") (part "R-EU_R0805"))
    )
    (comp (ref "R34")
      (value "10R")
      (footprint "eagle-import:R1206")
      (libsource (lib "eagle-import") (part "R-EU_R1206"))
    )
    (comp (ref "R35")
      (value "10R")
      (footprint "eagle-import:R1206")
      (libsource (lib "eagle-import") (part "R-EU_R1206"))
    )
    (comp (ref "R36")
      (value "4K7")
      (footprint "eagle-import:R0805")
      (libsource (lib "eagle-import") (part "R-EU_R0805"))
    )
    (comp (ref "R37")
      (value "220R")
      (footprint "eagle-import:R0805")
      (libsource (lib "eagle-import") (part "R-EU_R0805"))
    )
    (comp (ref "R38")
      (value "1K")
      (footprint "eagle-import:R0805")
      (libsource (lib "eagle-import") (part "R-EU_R0805"))
    )
    (comp (ref "R39")
      (value "220R")
      (footprint "eagle-import:R0805")
      (libsource (lib "eagle-import") (part "R-EU_R0805"))
    )
    (comp (ref "R40")
      (value "2K2")
      (footprint "eagle-import:R0805")
      (libsource (lib "eagle-import") (part "R-EU_R0805"))
    )
    (comp (ref "R41")
      (value "7K5 0.1%")
      (footprint "eagle-import:R0805")
      (libsource (lib "eagle-import") (part "R-EU_R0805"))
    )
    (comp (ref "R42")
      (value "22K")
      (footprint "eagle-import:R0805")
      (libsource (lib "eagle-import") (part "R-EU_R0805"))
    )
    (comp (ref "R43")
      (value "1K")
      (footprint "eagle-import:R0805")
      (libsource (lib "eagle-import") (part "R-EU_R0805"))
    )
    (comp (ref "R44")
      (value "16K")
      (footprint "eagle-import:R0805")
      (libsource (lib "eagle-import") (part "R-EU_R0805"))
    )
    (comp (ref "R45")
      (value "124K 0.1%")
      (footprint "eagle-import:R0805")
      (libsource (lib "eagle-import") (part "R-EU_R0805"))
    )
    (comp (ref "R46")
      (value "124K 0.1%")
      (footprint "eagle-import:R0805")
      (libsource (lib "eagle-import") (part "R-EU_R0805"))
    )
    (comp (ref "R47")
      (value "10K")
      (footprint "eagle-import:R0805")
      (libsource (lib "eagle-import") (part "R-EU_R0805"))
    )
    (comp (ref "R48")
      (value "2K2")
      (footprint "eagle-import:R0805")
      (libsource (lib "eagle-import") (part "R-EU_R0805"))
    )
    (comp (ref "R49")
      (value "15R")
      (footprint "eagle-import:R2010")
      (libsource (lib "eagle-import") (part "R-EU_R2010"))
    )
    (comp (ref "R50")
      (value "7K5 0.1%")
      (footprint "eagle-import:R0805")
      (libsource (lib "eagle-import") (part "R-EU_R0805"))
    )
    (comp (ref "R51")
      (value "N.C.")
      (footprint "eagle-import:R0805")
      (libsource (lib "eagle-import") (part "R-EU_R0805"))
    )
    (comp (ref "R52")
      (value "10K")
      (footprint "eagle-import:R0805")
      (libsource (lib "eagle-import") (part "R-EU_R0805"))
    )
    (comp (ref "R53")
      (value "16K")
      (footprint "eagle-import:R0805")
      (libsource (lib "eagle-import") (part "R-EU_R0805"))
    )
    (comp (ref "R54")
      (value "4K7")
      (footprint "eagle-import:R0805")
      (libsource (lib "eagle-import") (part "R-EU_R0805"))
    )
    (comp (ref "R55")
      (value "N.C.")
      (footprint "eagle-import:R0805")
      (libsource (lib "eagle-import") (part "R-EU_R0805"))
    )
    (comp (ref "R56")
      (value "2K2")
      (footprint "eagle-import:R0805")
      (libsource (lib "eagle-import") (part "R-EU_R0805"))
    )
    (comp (ref "R57")
      (value "2K2")
      (footprint "eagle-import:R0805")
      (libsource (lib "eagle-import") (part "R-EU_R0805"))
    )
    (comp (ref "R58")
      (value "39K 0.1%")
      (footprint "eagle-import:R0805")
      (libsource (lib "eagle-import") (part "R-EU_R0805"))
    )
    (comp (ref "R59")
      (value "820R 0.1%")
      (footprint "eagle-import:R0805")
      (libsource (lib "eagle-import") (part "R-EU_R0805"))
    )
    (comp (ref "R60")
      (value "47K")
      (footprint "eagle-import:R0805")
      (libsource (lib "eagle-import") (part "R-EU_R0805"))
    )
    (comp (ref "R61")
      (value "1R")
      (footprint "eagle-import:R1206")
      (libsource (lib "eagle-import") (part "R-EU_R1206"))
    )
    (comp (ref "R62")
      (value "10K")
      (footprint "eagle-import:R0805")
      (libsource (lib "eagle-import") (part "R-EU_R0805"))
    )
    (comp (ref "R63")
      (value "220R")
      (footprint "eagle-import:R0805")
      (libsource (lib "eagle-import") (part "R-EU_R0805"))
    )
    (comp (ref "R64")
      (value "39K 0.1%")
      (footprint "eagle-import:R0805")
      (libsource (lib "eagle-import") (part "R-EU_R0805"))
    )
    (comp (ref "R65")
      (value "47K")
      (footprint "eagle-import:R0805")
      (libsource (lib "eagle-import") (part "R-EU_R0805"))
    )
    (comp (ref "R66")
      (value "750R")
      (footprint "eagle-import:R0805")
      (libsource (lib "eagle-import") (part "R-EU_R0805"))
    )
    (comp (ref "R67")
      (value "0R010 (low TCR)")
      (footprint "eagle-import:R_2512-4WIRE")
      (libsource (lib "eagle-import") (part "R-EU_4WIRE2512"))
    )
    (comp (ref "R68")
      (value "820R 0.1%")
      (footprint "eagle-import:R0805")
      (libsource (lib "eagle-import") (part "R-EU_R0805"))
    )
    (comp (ref "ZD2")
      (value "MM3Z9V1T1G")
      (footprint "eagle-import:SOD323-R")
      (libsource (lib "eagle-import") (part "ZENER-DIODESOD323R"))
    )
    (comp (ref "C20")
      (value "4u7")
      (footprint "eagle-import:C1206")
      (libsource (lib "eagle-import") (part "C-EUC1206"))
    )
    (comp (ref "C21")
      (value "4u7")
      (footprint "eagle-import:C1206")
      (libsource (lib "eagle-import") (part "C-EUC1206"))
    )
    (comp (ref "C22")
      (value "2u2")
      (footprint "eagle-import:C1206")
      (libsource (lib "eagle-import") (part "C-EUC1206"))
    )
    (comp (ref "C23")
      (value "2u2")
      (footprint "eagle-import:C1206")
      (libsource (lib "eagle-import") (part "C-EUC1206"))
    )
    (comp (ref "C24")
      (value "100n")
      (footprint "eagle-import:C0603")
      (libsource (lib "eagle-import") (part "C-EUC0603"))
    )
    (comp (ref "C25")
      (value "330p")
      (footprint "eagle-import:C0805")
      (libsource (lib "eagle-import") (part "C-EUC0805"))
    )
    (comp (ref "C26")
      (value "22u")
      (footprint "eagle-import:C1210")
      (libsource (lib "eagle-import") (part "C-EUC1210"))
    )
    (comp (ref "C27")
      (value "4u7")
      (footprint "eagle-import:C1206")
      (libsource (lib "eagle-import") (part "C-EUC1206"))
    )
    (comp (ref "C28")
      (value "10n")
      (footprint "eagle-import:C0805")
      (libsource (lib "eagle-import") (part "C-EUC0805"))
    )
    (comp (ref "C29")
      (value "33p")
      (footprint "eagle-import:C0805")
      (libsource (lib "eagle-import") (part "C-EUC0805"))
    )
    (comp (ref "C30")
      (value "100n")
      (footprint "eagle-import:C0603")
      (libsource (lib "eagle-import") (part "C-EUC0603"))
    )
    (comp (ref "C31")
      (value "100n")
      (footprint "eagle-import:C0603")
      (libsource (lib "eagle-import") (part "C-EUC0603"))
    )
    (comp (ref "C32")
      (value "100n")
      (footprint "eagle-import:C0603")
      (libsource (lib "eagle-import") (part "C-EUC0603"))
    )
    (comp (ref "C33")
      (value "10n")
      (footprint "eagle-import:C0805")
      (libsource (lib "eagle-import") (part "C-EUC0805"))
    )
    (comp (ref "C34")
      (value "100n")
      (footprint "eagle-import:C0603")
      (libsource (lib "eagle-import") (part "C-EUC0603"))
    )
    (comp (ref "C35")
      (value "100n")
      (footprint "eagle-import:C0603")
      (libsource (lib "eagle-import") (part "C-EUC0603"))
    )
    (comp (ref "C36")
      (value "100n")
      (footprint "eagle-import:C0603")
      (libsource (lib "eagle-import") (part "C-EUC0603"))
    )
    (comp (ref "C37")
      (value "100n")
      (footprint "eagle-import:C0603")
      (libsource (lib "eagle-import") (part "C-EUC0603"))
    )
    (comp (ref "C38")
      (value "100n")
      (footprint "eagle-import:C0603")
      (libsource (lib "eagle-import") (part "C-EUC0603"))
    )
    (comp (ref "D4")
      (value "SKL16")
      (footprint "eagle-import:SOD123")
      (libsource (lib "eagle-import") (part "SCHOTTKYSOD123"))
    )
    (comp (ref "D5")
      (value "SKL16")
      (footprint "eagle-import:SOD123")
      (libsource (lib "eagle-import") (part "SCHOTTKYSOD123"))
    )
    (comp (ref "D6")
      (value "SKL14")
      (footprint "eagle-import:SOD123")
      (libsource (lib "eagle-import") (part "SCHOTTKYSOD123"))
    )
    (comp (ref "D7")
      (value "SKL14")
      (footprint "eagle-import:SOD123")
      (libsource (lib "eagle-import") (part "SCHOTTKYSOD123"))
    )
    (comp (ref "FB1")
      (value "60R@100MHz")
      (footprint "eagle-import:BEAD0603")
      (libsource (lib "eagle-import") (part "FERRITE_BEAD0603"))
    )
    (comp (ref "FB2")
      (value "60R@100MHz")
      (footprint "eagle-import:BEAD0603")
      (libsource (lib "eagle-import") (part "FERRITE_BEAD0603"))
    )
    (comp (ref "FB3")
      (value "60R@100MHz")
      (footprint "eagle-import:BEAD0603")
      (libsource (lib "eagle-import") (part "FERRITE_BEAD0603"))
    )
    (comp (ref "IC2")
      (value "TPS54060DGQ")
      (footprint "eagle-import:SOP50P490X110-11N")
      (fields (field (name "MPN") "TPS54060ADGQ"))
      (libsource (lib "eagle-import") (part "TPS54060DGQ"))
    )
    (comp (ref "IC3")
      (value "SI8641BB-B-IS1")
      (footprint "eagle-import:SOIC-16")
      (libsource (lib "eagle-import") (part "SI8641NSOIC-16"))
    )
    (comp (ref "IC4")
      (value "SN74LVC1G139DCUR")
      (footprint "eagle-import:DCU8")
      (libsource (lib "eagle-import") (part "SN74LVC1G139-VSSOP"))
    )
    (comp (ref "IC5")
      (value "MC78L05")
      (footprint "eagle-import:SOIC127P600X173-8N")
      (libsource (lib "eagle-import") (part "MC78LXXSOIC8"))
    )
    (comp (ref "IC6")
      (value "MC79L05")
      (footprint "eagle-import:SOIC127P600X173-8N")
      (libsource (lib "eagle-import") (part "MC79LXXSOIC"))
    )
    (comp (ref "IC7")
      (value "SI8641BB-B-IS1")
      (footprint "eagle-import:SOIC-16")
      (libsource (lib "eagle-import") (part "SI8641NSOIC-16"))
    )
    (comp (ref "IC8")
      (value "M24C32-WMN6P")
      (footprint "eagle-import:SOIC127P600X173-8N")
      (libsource (lib "eagle-import") (part "AT24CXXSOIC8"))
    )
    (comp (ref "KK1")
      (value "PMB-1")
      (footprint "eagle-import:PCB-MB")
      (libsource (lib "eagle-import") (part "PCB-MB"))
    )
    (comp (ref "KK2")
      (value "PMB-1")
      (footprint "eagle-import:PCB-MB")
      (libsource (lib "eagle-import") (part "PCB-MB"))
    )
    (comp (ref "R12")
      (value "10R")
      (footprint "eagle-import:R1206")
      (libsource (lib "eagle-import") (part "R-EU_R1206"))
    )
    (comp (ref "R13")
      (value "47K")
      (footprint "eagle-import:R0805")
      (libsource (lib "eagle-import") (part "R-EU_R0805"))
    )
    (comp (ref "R14")
      (value "10R")
      (footprint "eagle-import:R1206")
      (libsource (lib "eagle-import") (part "R-EU_R1206"))
    )
    (comp (ref "R15")
      (value "10R")
      (footprint "eagle-import:R1206")
      (libsource (lib "eagle-import") (part "R-EU_R1206"))
    )
    (comp (ref "R16")
      (value "2K2")
      (footprint "eagle-import:R0805")
      (libsource (lib "eagle-import") (part "R-EU_R0805"))
    )
    (comp (ref "R17")
      (value "10K")
      (footprint "eagle-import:R0805")
      (libsource (lib "eagle-import") (part "R-EU_R0805"))
    )
    (comp (ref "R18")
      (value "100K")
      (footprint "eagle-import:R0805")
      (libsource (lib "eagle-import") (part "R-EU_R0805"))
    )
    (comp (ref "R19")
      (value "330K")
      (footprint "eagle-import:R0805")
      (libsource (lib "eagle-import") (part "R-EU_R0805"))
    )
    (comp (ref "R20")
      (value "86K6")
      (footprint "eagle-import:R0805")
      (libsource (lib "eagle-import") (part "R-EU_R0805"))
    )
    (comp (ref "R21")
      (value "10K")
      (footprint "eagle-import:R0805")
      (libsource (lib "eagle-import") (part "R-EU_R0805"))
    )
    (comp (ref "R22")
      (value "10K")
      (footprint "eagle-import:R0805")
      (libsource (lib "eagle-import") (part "R-EU_R0805"))
    )
    (comp (ref "R23")
      (value "10K")
      (footprint "eagle-import:R0805")
      (libsource (lib "eagle-import") (part "R-EU_R0805"))
    )
    (comp (ref "R24")
      (value "10K")
      (footprint "eagle-import:R0805")
      (libsource (lib "eagle-import") (part "R-EU_R0805"))
    )
    (comp (ref "RN1")
      (value "DR1206-33R-4/8")
      (footprint "eagle-import:CAY16")
      (libsource (lib "eagle-import") (part "R_ARRAY4"))
    )
    (comp (ref "RN2")
      (value "DR1206-33R-4/8")
      (footprint "eagle-import:CAY16")
      (libsource (lib "eagle-import") (part "R_ARRAY4"))
    )
    (comp (ref "TR1")
      (value "SRF0703-821M")
      (footprint "eagle-import:SRF0703")
      (libsource (lib "eagle-import") (part "BOURNS_SRF0703INV"))
    )
    (comp (ref "X2")
      (value "77317-104-20LF")
      (footprint "eagle-import:77317-104-28LF")
      (libsource (lib "eagle-import") (part "77317-104-28LF"))
    )
    (comp (ref "C90")
      (value "10n")
      (footprint "eagle-import:C0805")
      (libsource (lib "eagle-import") (part "C-EUC0805"))
    )
    (comp (ref "C91")
      (value "470n")
      (footprint "eagle-import:C0805")
      (libsource (lib "eagle-import") (part "C-EUC0805"))
    )
    (comp (ref "C92")
      (value "HHXC630A330MHA0G")
      (footprint "eagle-import:CAPAE830X1050N")
      (libsource (lib "eagle-import") (part "ECAPSMD8.3MM/HA0"))
    )
    (comp (ref "C93")
      (value "10n/200V")
      (footprint "eagle-import:C1206")
      (libsource (lib "eagle-import") (part "C-EUC1206"))
    )
    (comp (ref "C94")
      (value "N.C.")
      (footprint "eagle-import:ECAP2_5")
      (libsource (lib "eagle-import") (part "ECAP2G/5"))
    )
    (comp (ref "C95")
      (value "N.C.")
      (footprint "eagle-import:C0805")
      (libsource (lib "eagle-import") (part "C-EUC0805"))
    )
    (comp (ref "C96")
      (value "N.C.")
      (footprint "eagle-import:C0805")
      (libsource (lib "eagle-import") (part "C-EUC0805"))
    )
    (comp (ref "C97")
      (value "10n/200V")
      (footprint "eagle-import:C1206")
      (libsource (lib "eagle-import") (part "C-EUC1206"))
    )
    (comp (ref "C98")
      (value "10n")
      (footprint "eagle-import:C0805")
      (libsource (lib "eagle-import") (part "C-EUC0805"))
    )
    (comp (ref "D20")
      (value "BAS316")
      (footprint "eagle-import:SOD323-R")
      (libsource (lib "eagle-import") (part "DIODESOD323R"))
    )
    (comp (ref "F1")
      (value "ZH32")
      (footprint "eagle-import:ZH32")
      (libsource (lib "eagle-import") (part "ZH32"))
    )
    (comp (ref "F2")
      (value "ZH32")
      (footprint "eagle-import:ZH32")
      (libsource (lib "eagle-import") (part "ZH32"))
    )
    (comp (ref "J2")
      (value "FCR7350R")
      (footprint "eagle-import:S16N-PC")
      (libsource (lib "eagle-import") (part "BINDING_POSTCLIFF"))
    )
    (comp (ref "J3")
      (value "FCR7350B")
      (footprint "eagle-import:S16N-PC")
      (libsource (lib "eagle-import") (part "BINDING_POSTCLIFF"))
    )
    (comp (ref "JP3")
      (value "JP2-CUT-0805")
      (footprint "eagle-import:R_0805")
      (libsource (lib "eagle-import") (part "JP2-CUT-0805"))
    )
    (comp (ref "JP4")
      (value "JP2-CUT-0805")
      (footprint "eagle-import:R_0805")
      (libsource (lib "eagle-import") (part "JP2-CUT-0805"))
    )
    (comp (ref "K1")
      (value "G6K-2F-5DC")
      (footprint "eagle-import:G6K-2F")
      (fields
        (field (name "MF") "OMRON COMPONENTS USA")
        (field (name "MPN") "G6K-2F DC24")
        (field (name "MF_1") "OMRON COMPONENTS USA")
        (field (name "MPN_1") "G6K-2F DC24")
        (field (name "OC_FARNELL") "1690427")
        (field (name "OC_NEWARK") "36K7467")
      )
      (libsource (lib "eagle-import") (part "G6K-2F"))
    )
    (comp (ref "Q20")
      (value "MMBT5401")
      (footprint "eagle-import:SOT23-BEC")
      (libsource (lib "eagle-import") (part "-PNP-SOT23-BECBC857B"))
    )
    (comp (ref "Q21")
      (value "MMBT5551")
      (footprint "eagle-import:SOT23-BEC")
      (libsource (lib "eagle-import") (part "-NPN-SOT23-BECMMBT5551LT1"))
    )
    (comp (ref "Q22")
      (value "MMBT5551")
      (footprint "eagle-import:SOT23-BEC")
      (libsource (lib "eagle-import") (part "-NPN-SOT23-BECMMBT5551LT1"))
    )
    (comp (ref "Q23")
      (value "2N7002")
      (footprint "eagle-import:SOT103P240X110-3N")
      (fields
        (field (name "MPN") "2N7002-7-F")
        (field (name "MPN_1") "2N7002-7-F")
        (field (name "OC_FARNELL") "1713823")
        (field (name "OC_NEWARK") "25R5679")
        (field (name "PACKAGE") "SOT-23-3")
        (field (name "SUPPLIER") "DIODES INC.")
      )
      (libsource (lib "eagle-import") (part "2N7002"))
    )
    (comp (ref "R104")
      (value "330R")
      (footprint "eagle-import:R0805")
      (libsource (lib "eagle-import") (part "R-EU_R0805"))
    )
    (comp (ref "R105")
      (value "750R")
      (footprint "eagle-import:R0805")
      (libsource (lib "eagle-import") (part "R-EU_R0805"))
    )
    (comp (ref "R106")
      (value "3K3")
      (footprint "eagle-import:R0805")
      (libsource (lib "eagle-import") (part "R-EU_R0805"))
    )
    (comp (ref "R107")
      (value "10K")
      (footprint "eagle-import:R0805")
      (libsource (lib "eagle-import") (part "R-EU_R0805"))
    )
    (comp (ref "R108")
      (value "10K")
      (footprint "eagle-import:R0805")
      (libsource (lib "eagle-import") (part "R-EU_R0805"))
    )
    (comp (ref "R109")
      (value "1R")
      (footprint "eagle-import:R1206")
      (libsource (lib "eagle-import") (part "R-EU_R1206"))
    )
    (comp (ref "R110")
      (value "750R")
      (footprint "eagle-import:R0805")
      (libsource (lib "eagle-import") (part "R-EU_R0805"))
    )
    (comp (ref "R111")
      (value "47K")
      (footprint "eagle-import:R0805")
      (libsource (lib "eagle-import") (part "R-EU_R0805"))
    )
    (comp (ref "R112")
      (value "330R")
      (footprint "eagle-import:R0805")
      (libsource (lib "eagle-import") (part "R-EU_R0805"))
    )
    (comp (ref "R113")
      (value "470R")
      (footprint "eagle-import:R0805")
      (libsource (lib "eagle-import") (part "R-EU_R0805"))
    )
    (comp (ref "R114")
      (value "100K")
      (footprint "eagle-import:R0805")
      (libsource (lib "eagle-import") (part "R-EU_R0805"))
    )
    (comp (ref "X4")
      (value "DS1024-2*10R0")
      (footprint "eagle-import:SSW-110-02-T-D-RA")
      (libsource (lib "eagle-import") (part "SSW-110-02-T-D-RA"))
    )
    (comp (ref "ZD5")
      (value "SMAJ51A")
      (footprint "eagle-import:DO214AA")
      (libsource (lib "eagle-import") (part "P6SMB68A"))
    )
  )
  (nets
    (net (code "1") (name "+3V3") (class "Default")
      (node (ref "C30") (pin "1") (pinfunction "1_1") (pintype "passive"))
      (node (ref "C35") (pin "1") (pinfunction "1_1") (pintype "passive"))
      (node (ref "C38") (pin "2") (pinfunction "2_2") (pintype "passive"))
      (node (ref "IC3") (pin "1") (pinfunction "VDD1_1") (pintype "passive"))
      (node (ref "IC3") (pin "7") (pinfunction "EN1_7") (pintype "input"))
      (node (ref "IC7") (pin "1") (pinfunction "VDD1_1") (pintype "passive"))
      (node (ref "IC7") (pin "7") (pinfunction "EN1_7") (pintype "input"))
      (node (ref "IC8") (pin "8") (pinfunction "VCC_8") (pintype "power_in"))
      (node (ref "R22") (pin "1") (pinfunction "1_1") (pintype "passive"))
      (node (ref "R23") (pin "1") (pinfunction "1_1") (pintype "passive"))
      (node (ref "R24") (pin "1") (pinfunction "1_1") (pintype "passive"))
      (node (ref "X2") (pin "1") (pinfunction "1_1") (pintype "passive"))
    )
    (net (code "2") (name "+5V") (class "Default")
      (node (ref "C31") (pin "2") (pinfunction "2_2") (pintype "passive"))
      (node (ref "C32") (pin "1") (pinfunction "1_1") (pintype "passive"))
      (node (ref "C36") (pin "2") (pinfunction "2_2") (pintype "passive"))
      (node (ref "C63") (pin "2") (pinfunction "2_2") (pintype "passive"))
      (node (ref "C64") (pin "2") (pinfunction "2_2") (pintype "passive"))
      (node (ref "C65") (pin "2") (pinfunction "2_2") (pintype "passive"))
      (node (ref "C66") (pin "1") (pinfunction "1_1") (pintype "passive"))
      (node (ref "C68") (pin "1") (pinfunction "1_1") (pintype "passive"))
      (node (ref "C79") (pin "2") (pinfunction "2_2") (pintype "passive"))
      (node (ref "C80") (pin "2") (pinfunction "2_2") (pintype "passive"))
      (node (ref "D20") (pin "C") (pinfunction "C_C") (pintype "passive"))
      (node (ref "FB2") (pin "P$2") (pinfunction "2_P$2") (pintype "passive"))
      (node (ref "IC12") (pin "7") (pinfunction "~{PRE}_7") (pintype "input"))
      (node (ref "IC12") (pin "8") (pinfunction "VDD_8") (pintype "power_in"))
      (node (ref "IC13") (pin "9") (pinfunction "VDD_9") (pintype "power_in"))
      (node (ref "IC15") (pin "5") (pinfunction "VDD_5") (pintype "passive"))
      (node (ref "IC18") (pin "13") (pinfunction "DVDD_13") (pintype "power_in"))
      (node (ref "IC3") (pin "10") (pinfunction "EN2_10") (pintype "input"))
      (node (ref "IC3") (pin "16") (pinfunction "VDD2_16") (pintype "passive"))
      (node (ref "IC4") (pin "8") (pinfunction "VCC_8") (pintype "passive"))
      (node (ref "IC7") (pin "10") (pinfunction "EN2_10") (pintype "input"))
      (node (ref "IC7") (pin "16") (pinfunction "VDD2_16") (pintype "passive"))
      (node (ref "K1") (pin "1") (pinfunction "+_1") (pintype "passive"))
      (node (ref "LED2") (pin "TA") (pinfunction "A_TA") (pintype "passive"))
      (node (ref "LED3") (pin "BA") (pinfunction "A_BA") (pintype "passive"))
      (node (ref "LED3") (pin "TA") (pinfunction "A_TA") (pintype "passive"))
      (node (ref "Q12") (pin "2") (pinfunction "S_2") (pintype "passive"))
      (node (ref "R107") (pin "2") (pinfunction "2_2") (pintype "passive"))
      (node (ref "R17") (pin "1") (pinfunction "1_1") (pintype "passive"))
      (node (ref "R69") (pin "1") (pinfunction "1_1") (pintype "passive"))
      (node (ref "R70") (pin "1") (pinfunction "1_1") (pintype "passive"))
      (node (ref "R71") (pin "1") (pinfunction "1_1") (pintype "passive"))
      (node (ref "R72") (pin "1") (pinfunction "1_1") (pintype "passive"))
      (node (ref "R84") (pin "2") (pinfunction "2_2") (pintype "passive"))
      (node (ref "R98") (pin "2") (pinfunction "2_2") (pintype "passive"))
    )
    (net (code "3") (name "+VNR") (class "Default")
      (node (ref "C27") (pin "1") (pinfunction "1_1") (pintype "passive"))
      (node (ref "IC5") (pin "8") (pinfunction "VI_8") (pintype "input"))
      (node (ref "R14") (pin "1") (pinfunction "1_1") (pintype "passive"))
    )
    (net (code "4") (name "+VREF") (class "Default")
      (node (ref "C69") (pin "+") (pinfunction "+_+") (pintype "passive"))
      (node (ref "C73") (pin "2") (pinfunction "2_2") (pintype "passive"))
      (node (ref "C83") (pin "2") (pinfunction "2_2") (pintype "passive"))
      (node (ref "IC14") (pin "6") (pinfunction "VOUT_6") (pintype "output"))
      (node (ref "IC16") (pin "2") (pinfunction "VREF_2") (pintype "input"))
      (node (ref "IC18") (pin "9") (pinfunction "REFP0_9") (pintype "input"))
      (node (ref "R31") (pin "1") (pinfunction "1_1") (pintype "passive"))
    )
    (net (code "5") (name "-9V") (class "Default")
      (node (ref "C21") (pin "1") (pinfunction "1_1") (pintype "passive"))
      (node (ref "IC6") (pin "2") (pinfunction "IN_2") (pintype "input"))
      (node (ref "IC6") (pin "3") (pinfunction "IN_3") (pintype "input"))
      (node (ref "IC6") (pin "6") (pinfunction "IN_6") (pintype "input"))
      (node (ref "IC6") (pin "7") (pinfunction "IN_7") (pintype "input"))
      (node (ref "R12") (pin "1") (pinfunction "1_1") (pintype "passive"))
      (node (ref "R28") (pin "1") (pinfunction "1_1") (pintype "passive"))
      (node (ref "R38") (pin "2") (pinfunction "2_2") (pintype "passive"))
      (node (ref "R39") (pin "2") (pinfunction "2_2") (pintype "passive"))
    )
    (net (code "6") (name "AUX_USET_SW") (class "Default")
      (node (ref "IC13") (pin "4") (pinfunction "GPB3_4") (pintype "bidirectional"))
      (node (ref "IC17") (pin "6") (pinfunction "CTRL_6") (pintype "input"))
      (node (ref "LED2") (pin "BA") (pinfunction "A_BA") (pintype "passive"))
    )
    (net (code "7") (name "CC_ACTIVE") (class "Default")
      (node (ref "IC13") (pin "22") (pinfunction "GPA1_22") (pintype "bidirectional"))
      (node (ref "Q16") (pin "1") (pinfunction "G_1") (pintype "passive"))
      (node (ref "R100") (pin "2") (pinfunction "2_2") (pintype "passive"))
      (node (ref "R98") (pin "1") (pinfunction "1_1") (pintype "passive"))
    )
    (net (code "8") (name "CSA") (class "Default")
      (node (ref "IC3") (pin "13") (pinfunction "B2_13") (pintype "output"))
      (node (ref "IC4") (pin "1") (pinfunction "A_1") (pintype "input"))
    )
    (net (code "9") (name "CSB") (class "Default")
      (node (ref "IC3") (pin "12") (pinfunction "B3_12") (pintype "output"))
      (node (ref "IC4") (pin "2") (pinfunction "B_2") (pintype "input"))
    )
    (net (code "10") (name "CS_ADC") (class "Default")
      (node (ref "IC18") (pin "2") (pinfunction "~{CS}_2") (pintype "input"))
      (node (ref "RN1") (pin "7") (pinfunction "2_7") (pintype "passive"))
    )
    (net (code "11") (name "CS_DAC") (class "Default")
      (node (ref "IC16") (pin "5") (pinfunction "~{SYNC}_5") (pintype "input"))
      (node (ref "RN1") (pin "8") (pinfunction "2_8") (pintype "passive"))
    )
    (net (code "12") (name "CS_IOEXP") (class "Default")
      (node (ref "IC13") (pin "11") (pinfunction "~{CS}_11") (pintype "input"))
      (node (ref "RN1") (pin "6") (pinfunction "2_6") (pintype "passive"))
    )
    (net (code "13") (name "CURR_5A") (class "Default")
      (node (ref "IC13") (pin "28") (pinfunction "GPA7_28") (pintype "bidirectional"))
      (node (ref "Q11") (pin "4") (pinfunction "G_4") (pintype "passive"))
      (node (ref "R65") (pin "2") (pinfunction "2_2") (pintype "passive"))
    )
    (net (code "14") (name "CURR_50MA") (class "Default")
      (node (ref "IC13") (pin "27") (pinfunction "GPA6_27") (pintype "bidirectional"))
      (node (ref "Q10") (pin "4") (pinfunction "G_4") (pintype "passive"))
      (node (ref "R60") (pin "2") (pinfunction "2_2") (pintype "passive"))
    )
    (net (code "15") (name "CV_ACTIVE") (class "Default")
      (node (ref "IC13") (pin "23") (pinfunction "GPA2_23") (pintype "bidirectional"))
      (node (ref "Q15") (pin "1") (pinfunction "G_1") (pintype "passive"))
      (node (ref "R84") (pin "1") (pinfunction "1_1") (pintype "passive"))
      (node (ref "R88") (pin "2") (pinfunction "2_2") (pintype "passive"))
    )
    (net (code "16") (name "DC+") (class "Default")
      (node (ref "C1") (pin "2") (pinfunction "2_2") (pintype "passive"))
      (node (ref "L1") (pin "1") (pinfunction "1_1") (pintype "passive"))
      (node (ref "R1") (pin "2") (pinfunction "2_2") (pintype "passive"))
      (node (ref "X1") (pin "1") (pinfunction "1_1") (pintype "passive"))
    )
    (net (code "17") (name "DC-") (class "Default")
      (node (ref "C1") (pin "1") (pinfunction "1_1") (pintype "passive"))
      (node (ref "L1") (pin "3") (pinfunction "1_3") (pintype "passive"))
      (node (ref "R1") (pin "1") (pinfunction "1_1") (pintype "passive"))
      (node (ref "X1") (pin "2") (pinfunction "1_2") (pintype "passive"))
    )
    (net (code "18") (name "DC_OUT") (class "Default")
      (node (ref "C2") (pin "+") (pinfunction "+_+") (pintype "passive"))
      (node (ref "C22") (pin "1") (pinfunction "1_1") (pintype "passive"))
      (node (ref "C23") (pin "1") (pinfunction "1_1") (pintype "passive"))
      (node (ref "C4") (pin "2") (pinfunction "2_2") (pintype "passive"))
      (node (ref "C5") (pin "1") (pinfunction "1_1") (pintype "passive"))
      (node (ref "C6") (pin "1") (pinfunction "1_1") (pintype "passive"))
      (node (ref "C7") (pin "1") (pinfunction "1_1") (pintype "passive"))
      (node (ref "C8") (pin "2") (pinfunction "2_2") (pintype "passive"))
      (node (ref "IC1") (pin "11") (pinfunction "VIN_11") (pintype "passive"))
      (node (ref "IC2") (pin "2") (pinfunction "VIN_2") (pintype "power_in"))
      (node (ref "L1") (pin "2") (pinfunction "2_2") (pintype "passive"))
      (node (ref "R13") (pin "2") (pinfunction "2_2") (pintype "passive"))
      (node (ref "R3") (pin "1") (pinfunction "1_1") (pintype "passive"))
      (node (ref "ZD1") (pin "C") (pinfunction "C_C") (pintype "passive"))
    )
    (net (code "19") (name "DIB_A0") (class "Default")
      (node (ref "IC8") (pin "1") (pinfunction "A0_1") (pintype "input"))
      (node (ref "R24") (pin "2") (pinfunction "2_2") (pintype "passive"))
      (node (ref "X2") (pin "17") (pinfunction "1_17") (pintype "passive"))
    )
    (net (code "20") (name "DIB_A1") (class "Default")
      (node (ref "IC8") (pin "2") (pinfunction "A1_2") (pintype "input"))
      (node (ref "R23") (pin "2") (pinfunction "2_2") (pintype "passive"))
      (node (ref "X2") (pin "19") (pinfunction "1_19") (pintype "passive"))
    )
    (net (code "21") (name "DIB_A2") (class "Default")
      (node (ref "IC8") (pin "3") (pinfunction "A2_3") (pintype "input"))
      (node (ref "R22") (pin "2") (pinfunction "2_2") (pintype "passive"))
      (node (ref "X2") (pin "18") (pinfunction "1_18") (pintype "passive"))
    )
    (net (code "22") (name "DIB_CSA") (class "Default")
      (node (ref "IC3") (pin "4") (pinfunction "A2_4") (pintype "input"))
      (node (ref "X2") (pin "9") (pinfunction "1_9") (pintype "passive"))
    )
    (net (code "23") (name "DIB_CSB") (class "Default")
      (node (ref "IC3") (pin "5") (pinfunction "A3_5") (pintype "input"))
      (node (ref "X2") (pin "12") (pinfunction "1_12") (pintype "passive"))
    )
    (net (code "24") (name "DIB_IRQ") (class "Default")
      (node (ref "IC7") (pin "6") (pinfunction "A4_6") (pintype "output"))
      (node (ref "X2") (pin "10") (pinfunction "1_10") (pintype "passive"))
    )
    (net (code "25") (name "DIB_MISO") (class "Default")
      (node (ref "IC3") (pin "6") (pinfunction "A4_6") (pintype "output"))
      (node (ref "X2") (pin "14") (pinfunction "1_14") (pintype "passive"))
    )
    (net (code "26") (name "DIB_MOSI") (class "Default")
      (node (ref "IC7") (pin "3") (pinfunction "A1_3") (pintype "input"))
      (node (ref "X2") (pin "15") (pinfunction "1_15") (pintype "passive"))
    )
    (net (code "27") (name "DIB_NRESET") (class "Default")
      (node (ref "IC7") (pin "5") (pinfunction "A3_5") (pintype "input"))
      (node (ref "X2") (pin "4") (pinfunction "1_4") (pintype "passive"))
    )
    (net (code "28") (name "DIB_SCL") (class "Default")
      (node (ref "IC8") (pin "6") (pinfunction "SCL_6") (pintype "bidirectional"))
      (node (ref "X2") (pin "5") (pinfunction "1_5") (pintype "passive"))
    )
    (net (code "29") (name "DIB_SCLK") (class "Default")
      (node (ref "IC3") (pin "3") (pinfunction "A1_3") (pintype "input"))
      (node (ref "X2") (pin "13") (pinfunction "1_13") (pintype "passive"))
    )
    (net (code "30") (name "DIB_SDA") (class "Default")
      (node (ref "IC8") (pin "5") (pinfunction "SDA_5") (pintype "bidirectional"))
      (node (ref "X2") (pin "8") (pinfunction "1_8") (pintype "passive"))
    )
    (net (code "31") (name "FB") (class "Default")
      (node (ref "C19") (pin "1") (pinfunction "1_1") (pintype "passive"))
      (node (ref "IC1") (pin "5") (pinfunction "VFB_5") (pintype "input"))
      (node (ref "Q2") (pin "C") (pinfunction "C_C") (pintype "passive"))
      (node (ref "R11") (pin "1") (pinfunction "1_1") (pintype "passive"))
      (node (ref "R9") (pin "2") (pinfunction "2_2") (pintype "passive"))
    )
    (net (code "32") (name "GCOM") (class "Default")
      (node (ref "IC10") (pin "6") (pinfunction "-IN_6") (pintype "input"))
      (node (ref "IC10") (pin "7") (pinfunction "OUT_7") (pintype "output"))
      (node (ref "R41") (pin "1") (pinfunction "1_1") (pintype "passive"))
      (node (ref "R58") (pin "1") (pinfunction "1_1") (pintype "passive"))
    )
    (net (code "33") (name "GND") (class "Default")
      (node (ref "C20") (pin "2") (pinfunction "2_2") (pintype "passive"))
      (node (ref "C21") (pin "2") (pinfunction "2_2") (pintype "passive"))
      (node (ref "C22") (pin "2") (pinfunction "2_2") (pintype "passive"))
      (node (ref "C23") (pin "2") (pinfunction "2_2") (pintype "passive"))
      (node (ref "C26") (pin "2") (pinfunction "2_2") (pintype "passive"))
      (node (ref "C27") (pin "2") (pinfunction "2_2") (pintype "passive"))
      (node (ref "C28") (pin "2") (pinfunction "2_2") (pintype "passive"))
      (node (ref "C29") (pin "1") (pinfunction "1_1") (pintype "passive"))
      (node (ref "C31") (pin "1") (pinfunction "1_1") (pintype "passive"))
      (node (ref "C32") (pin "2") (pinfunction "2_2") (pintype "passive"))
      (node (ref "C33") (pin "1") (pinfunction "1_1") (pintype "passive"))
      (node (ref "C34") (pin "2") (pinfunction "2_2") (pintype "passive"))
      (node (ref "C36") (pin "1") (pinfunction "1_1") (pintype "passive"))
      (node (ref "C37") (pin "1") (pinfunction "1_1") (pintype "passive"))
      (node (ref "C39") (pin "2") (pinfunction "2_2") (pintype "passive"))
      (node (ref "C42") (pin "2") (pinfunction "2_2") (pintype "passive"))
      (node (ref "C48") (pin "2") (pinfunction "2_2") (pintype "passive"))
      (node (ref "C49") (pin "1") (pinfunction "1_1") (pintype "passive"))
      (node (ref "C50") (pin "2") (pinfunction "2_2") (pintype "passive"))
      (node (ref "C51") (pin "1") (pinfunction "1_1") (pintype "passive"))
      (node (ref "C52") (pin "1") (pinfunction "1_1") (pintype "passive"))
      (node (ref "C53") (pin "1") (pinfunction "1_1") (pintype "passive"))
      (node (ref "C54") (pin "1") (pinfunction "1_1") (pintype "passive"))
      (node (ref "C56") (pin "1") (pinfunction "1_1") (pintype "passive"))
      (node (ref "C57") (pin "2") (pinfunction "2_2") (pintype "passive"))
      (node (ref "C58") (pin "1") (pinfunction "1_1") (pintype "passive"))
      (node (ref "C59") (pin "1") (pinfunction "1_1") (pintype "passive"))
      (node (ref "C65") (pin "1") (pinfunction "1_1") (pintype "passive"))
      (node (ref "C66") (pin "2") (pinfunction "2_2") (pintype "passive"))
      (node (ref "C67") (pin "2") (pinfunction "2_2") (pintype "passive"))
      (node (ref "C68") (pin "2") (pinfunction "2_2") (pintype "passive"))
      (node (ref "C69") (pin "-") (pinfunction "-_-") (pintype "passive"))
      (node (ref "C70") (pin "2") (pinfunction "2_2") (pintype "passive"))
      (node (ref "C71") (pin "2") (pinfunction "2_2") (pintype "passive"))
      (node (ref "C72") (pin "1") (pinfunction "1_1") (pintype "passive"))
      (node (ref "C73") (pin "1") (pinfunction "1_1") (pintype "passive"))
      (node (ref "C74") (pin "2") (pinfunction "2_2") (pintype "passive"))
      (node (ref "C75") (pin "1") (pinfunction "1_1") (pintype "passive"))
      (node (ref "C76") (pin "1") (pinfunction "1_1") (pintype "passive"))
      (node (ref "C77") (pin "2") (pinfunction "2_2") (pintype "passive"))
      (node (ref "C78") (pin "1") (pinfunction "1_1") (pintype "passive"))
      (node (ref "C79") (pin "1") (pinfunction "1_1") (pintype "passive"))
      (node (ref "C80") (pin "1") (pinfunction "1_1") (pintype "passive"))
      (node (ref "C81") (pin "1") (pinfunction "1_1") (pintype "passive"))
      (node (ref "C82") (pin "1") (pinfunction "1_1") (pintype "passive"))
      (node (ref "C83") (pin "1") (pinfunction "1_1") (pintype "passive"))
      (node (ref "C84") (pin "2") (pinfunction "2_2") (pintype "passive"))
      (node (ref "C85") (pin "1") (pinfunction "1_1") (pintype "passive"))
      (node (ref "C86") (pin "1") (pinfunction "1_1") (pintype "passive"))
      (node (ref "C88") (pin "1") (pinfunction "1_1") (pintype "passive"))
      (node (ref "C89") (pin "1") (pinfunction "1_1") (pintype "passive"))
      (node (ref "D10") (pin "C") (pinfunction "C_C") (pintype "passive"))
      (node (ref "D17") (pin "A") (pinfunction "A_A") (pintype "passive"))
      (node (ref "D19") (pin "C") (pinfunction "C_C") (pintype "passive"))
      (node (ref "D5") (pin "A") (pinfunction "A_A") (pintype "passive"))
      (node (ref "D6") (pin "A") (pinfunction "A_A") (pintype "passive"))
      (node (ref "D7") (pin "C") (pinfunction "C_C") (pintype "passive"))
      (node (ref "D9") (pin "C") (pinfunction "C_C") (pintype "passive"))
      (node (ref "GND") (pin "1") (pinfunction "P$1_1") (pintype "bidirectional"))
      (node (ref "IC12") (pin "4") (pinfunction "VSS_4") (pintype "power_in"))
      (node (ref "IC13") (pin "10") (pinfunction "VSS_10") (pintype "power_in"))
      (node (ref "IC13") (pin "15") (pinfunction "A0_15") (pintype "input"))
      (node (ref "IC13") (pin "16") (pinfunction "A1_16") (pintype "input"))
      (node (ref "IC13") (pin "17") (pinfunction "A2_17") (pintype "input"))
      (node (ref "IC14") (pin "4") (pinfunction "GND_4") (pintype "passive"))
      (node (ref "IC15") (pin "2") (pinfunction "GND_2") (pintype "passive"))
      (node (ref "IC16") (pin "8") (pinfunction "GND_8") (pintype "power_in"))
      (node (ref "IC17") (pin "2") (pinfunction "GND_2") (pintype "passive"))
      (node (ref "IC18") (pin "3") (pinfunction "CLK_3") (pintype "bidirectional"))
      (node (ref "IC18") (pin "4") (pinfunction "DGND_4") (pintype "passive"))
      (node (ref "IC18") (pin "5") (pinfunction "AVSS_5") (pintype "passive"))
      (node (ref "IC18") (pin "8") (pinfunction "REFN0_8") (pintype "input"))
      (node (ref "IC2") (pin "9") (pinfunction "GND_9") (pintype "passive"))
      (node (ref "IC2") (pin "TP") (pinfunction "TP_TP") (pintype "passive"))
      (node (ref "IC20") (pin "4") (pinfunction "GND_4") (pintype "passive"))
      (node (ref "IC3") (pin "15") (pinfunction "GND2_15") (pintype "passive"))
      (node (ref "IC3") (pin "9") (pinfunction "GND2_2_9") (pintype "passive"))
      (node (ref "IC4") (pin "4") (pinfunction "GND_4") (pintype "passive"))
      (node (ref "IC5") (pin "2") (pinfunction "GND_2") (pintype "passive"))
      (node (ref "IC5") (pin "3") (pinfunction "GND_3") (pintype "passive"))
      (node (ref "IC5") (pin "6") (pinfunction "GND_6") (pintype "passive"))
      (node (ref "IC5") (pin "7") (pinfunction "GND_7") (pintype "passive"))
      (node (ref "IC6") (pin "5") (pinfunction "GND_5") (pintype "passive"))
      (node (ref "IC7") (pin "15") (pinfunction "GND2_15") (pintype "passive"))
      (node (ref "IC7") (pin "9") (pinfunction "GND2_2_9") (pintype "passive"))
      (node (ref "KK3") (pin "1") (pinfunction "1_1") (pintype "passive"))
      (node (ref "KK3") (pin "2") (pinfunction "2_2") (pintype "passive"))
      (node (ref "Q15") (pin "2") (pinfunction "S_2") (pintype "passive"))
      (node (ref "Q16") (pin "2") (pinfunction "S_2") (pintype "passive"))
      (node (ref "Q17") (pin "2") (pinfunction "S_2") (pintype "passive"))
      (node (ref "Q21") (pin "E") (pinfunction "E_E") (pintype "passive"))
      (node (ref "Q23") (pin "2") (pinfunction "S_2") (pintype "passive"))
      (node (ref "Q9") (pin "2") (pinfunction "S_2") (pintype "passive"))
      (node (ref "R111") (pin "1") (pinfunction "1_1") (pintype "passive"))
      (node (ref "R114") (pin "1") (pinfunction "1_1") (pintype "passive"))
      (node (ref "R15") (pin "1") (pinfunction "1_1") (pintype "passive"))
      (node (ref "R16") (pin "1") (pinfunction "1_1") (pintype "passive"))
      (node (ref "R19") (pin "1") (pinfunction "1_1") (pintype "passive"))
      (node (ref "R21") (pin "1") (pinfunction "1_1") (pintype "passive"))
      (node (ref "R37") (pin "2") (pinfunction "2_2") (pintype "passive"))
      (node (ref "R55") (pin "1") (pinfunction "1_1") (pintype "passive"))
      (node (ref "R60") (pin "1") (pinfunction "1_1") (pintype "passive"))
      (node (ref "R65") (pin "1") (pinfunction "1_1") (pintype "passive"))
      (node (ref "R73") (pin "2") (pinfunction "2_2") (pintype "passive"))
      (node (ref "R79") (pin "1") (pinfunction "1_1") (pintype "passive"))
      (node (ref "R87") (pin "1") (pinfunction "1_1") (pintype "passive"))
      (node (ref "R89") (pin "2") (pinfunction "2_2") (pintype "passive"))
      (node (ref "R96") (pin "1") (pinfunction "1_1") (pintype "passive"))
      (node (ref "R97") (pin "1") (pinfunction "1_1") (pintype "passive"))
      (node (ref "SH1") (pin "2") (pinfunction "GND_B_2") (pintype "bidirectional"))
      (node (ref "TR1") (pin "4") (pinfunction "4_4") (pintype "passive"))
      (node (ref "X3") (pin "2") (pinfunction "1_2") (pintype "passive"))
      (node (ref "ZD3") (pin "1") (pinfunction "A_1") (pintype "passive"))
      (node (ref "ZD3") (pin "2") (pinfunction "A_2") (pintype "passive"))
    )
    (net (code "34") (name "GNDIO") (class "Default")
      (node (ref "C30") (pin "2") (pinfunction "2_2") (pintype "passive"))
      (node (ref "C35") (pin "2") (pinfunction "2_2") (pintype "passive"))
      (node (ref "C38") (pin "1") (pinfunction "1_1") (pintype "passive"))
      (node (ref "IC3") (pin "2") (pinfunction "GND1_2_2") (pintype "passive"))
      (node (ref "IC3") (pin "8") (pinfunction "GND1_8") (pintype "passive"))
      (node (ref "IC7") (pin "2") (pinfunction "GND1_2_2") (pintype "passive"))
      (node (ref "IC7") (pin "8") (pinfunction "GND1_8") (pintype "passive"))
      (node (ref "IC8") (pin "4") (pinfunction "GND_4") (pintype "passive"))
      (node (ref "IC8") (pin "7") (pinfunction "WP_7") (pintype "input"))
      (node (ref "X2") (pin "11") (pinfunction "1_11") (pintype "passive"))
      (node (ref "X2") (pin "16") (pinfunction "1_16") (pintype "passive"))
      (node (ref "X2") (pin "20") (pinfunction "1_20") (pintype "passive"))
      (node (ref "X2") (pin "25") (pinfunction "1_25") (pintype "passive"))
      (node (ref "X2") (pin "7") (pinfunction "1_7") (pintype "passive"))
    )
    (net (code "35") (name "IRQ") (class "Default")
      (node (ref "IC13") (pin "20") (pinfunction "INTA_20") (pintype "output"))
      (node (ref "IC7") (pin "11") (pinfunction "B4_11") (pintype "input"))
    )
    (net (code "36") (name "ISENSE+") (class "Default")
      (node (ref "IC11") (pin "3") (pinfunction "+IN_3") (pintype "input"))
      (node (ref "R58") (pin "2") (pinfunction "2_2") (pintype "passive"))
      (node (ref "R59") (pin "2") (pinfunction "2_2") (pintype "passive"))
    )
    (net (code "37") (name "ISENSE-") (class "Default")
      (node (ref "C62") (pin "1") (pinfunction "1_1") (pintype "passive"))
      (node (ref "IC11") (pin "2") (pinfunction "-IN_2") (pintype "input"))
      (node (ref "R64") (pin "1") (pinfunction "1_1") (pintype "passive"))
      (node (ref "R68") (pin "2") (pinfunction "2_2") (pintype "passive"))
    )
    (net (code "38") (name "I_MON") (class "Default")
      (node (ref "C62") (pin "2") (pinfunction "2_2") (pintype "passive"))
      (node (ref "IC11") (pin "6") (pinfunction "OUT_6") (pintype "output"))
      (node (ref "R62") (pin "1") (pinfunction "1_1") (pintype "passive"))
      (node (ref "R64") (pin "2") (pinfunction "2_2") (pintype "passive"))
      (node (ref "R81") (pin "1") (pinfunction "1_1") (pintype "passive"))
    )
    (net (code "39") (name "I_SERVO") (class "Default")
      (node (ref "C55") (pin "2") (pinfunction "2_2") (pintype "passive"))
      (node (ref "C60") (pin "2") (pinfunction "2_2") (pintype "passive"))
      (node (ref "D13") (pin "C") (pinfunction "C_C") (pintype "passive"))
      (node (ref "IC10") (pin "1") (pinfunction "OUT_1") (pintype "output"))
      (node (ref "R99") (pin "1") (pinfunction "1_1") (pintype "passive"))
    )
    (net (code "40") (name "I_SET") (class "Default")
      (node (ref "I_SET") (pin "2") (pinfunction "2_2") (pintype "passive"))
      (node (ref "R57") (pin "1") (pinfunction "1_1") (pintype "passive"))
      (node (ref "R77") (pin "1") (pinfunction "1_1") (pintype "passive"))
    )
    (net (code "41") (name "LOOP_CTRL") (class "Default")
      (node (ref "D12") (pin "A") (pinfunction "A_A") (pintype "passive"))
      (node (ref "D13") (pin "A") (pinfunction "A_A") (pintype "passive"))
      (node (ref "R40") (pin "1") (pinfunction "1_1") (pintype "passive"))
      (node (ref "R43") (pin "1") (pinfunction "1_1") (pintype "passive"))
      (node (ref "R94") (pin "2") (pinfunction "2_2") (pintype "passive"))
    )
    (net (code "42") (name "MISO") (class "Default")
      (node (ref "IC13") (pin "14") (pinfunction "SO_14") (pintype "output"))
      (node (ref "IC15") (pin "4") (pinfunction "SI/O_4") (pintype "bidirectional"))
      (node (ref "IC18") (pin "15") (pinfunction "DOUT/~{DRDY}_15") (pintype "output"))
      (node (ref "RN2") (pin "7") (pinfunction "2_7") (pintype "passive"))
    )
    (net (code "43") (name "MOSI") (class "Default")
      (node (ref "IC13") (pin "13") (pinfunction "SI_13") (pintype "input"))
      (node (ref "IC16") (pin "7") (pinfunction "DIN_7") (pintype "input"))
      (node (ref "IC18") (pin "16") (pinfunction "DIN_16") (pintype "input"))
      (node (ref "RN2") (pin "6") (pinfunction "2_6") (pintype "passive"))
    )
    (net (code "44") (name "Net-(C10-Pad1)") (class "Default")
      (node (ref "C10") (pin "1") (pinfunction "1_1") (pintype "passive"))
      (node (ref "C11") (pin "+") (pinfunction "+_+") (pintype "passive"))
      (node (ref "C15") (pin "1") (pinfunction "1_1") (pintype "passive"))
      (node (ref "C16") (pin "+") (pinfunction "+_+") (pintype "passive"))
      (node (ref "L2") (pin "2") (pinfunction "2_2") (pintype "passive"))
      (node (ref "L3") (pin "1") (pinfunction "1_1") (pintype "passive"))
      (node (ref "R4") (pin "1") (pinfunction "1_1") (pintype "passive"))
      (node (ref "R6") (pin "1") (pinfunction "1_1") (pintype "passive"))
      (node (ref "R7") (pin "1") (pinfunction "1_1") (pintype "passive"))
      (node (ref "R9") (pin "1") (pinfunction "1_1") (pintype "passive"))
    )
    (net (code "45") (name "Net-(C12-Pad2)") (class "Default")
      (node (ref "C12") (pin "2") (pinfunction "2_2") (pintype "passive"))
      (node (ref "R5") (pin "2") (pinfunction "2_2") (pintype "passive"))
    )
    (net (code "46") (name "Net-(C18-Pad1)") (class "Default")
      (node (ref "C18") (pin "1") (pinfunction "1_1") (pintype "passive"))
      (node (ref "R8") (pin "1") (pinfunction "1_1") (pintype "passive"))
    )
    (net (code "47") (name "Net-(C19-Pad2)") (class "Default")
      (node (ref "C19") (pin "2") (pinfunction "2_2") (pintype "passive"))
      (node (ref "D3") (pin "A") (pinfunction "A_A") (pintype "passive"))
      (node (ref "Q2") (pin "B") (pinfunction "B_B") (pintype "passive"))
      (node (ref "R10") (pin "1") (pinfunction "1_1") (pintype "passive"))
      (node (ref "R7") (pin "2") (pinfunction "2_2") (pintype "passive"))
    )
    (net (code "48") (name "Net-(C20-Pad1)") (class "Default")
      (node (ref "C20") (pin "1") (pinfunction "1_1") (pintype "passive"))
      (node (ref "D4") (pin "A") (pinfunction "A_A") (pintype "passive"))
      (node (ref "R12") (pin "2") (pinfunction "2_2") (pintype "passive"))
    )
    (net (code "49") (name "Net-(C25-Pad2)") (class "Default")
      (node (ref "C25") (pin "2") (pinfunction "2_2") (pintype "passive"))
      (node (ref "R15") (pin "2") (pinfunction "2_2") (pintype "passive"))
    )
    (net (code "50") (name "Net-(C26-Pad1)") (class "Default")
      (node (ref "C26") (pin "1") (pinfunction "1_1") (pintype "passive"))
      (node (ref "R14") (pin "2") (pinfunction "2_2") (pintype "passive"))
      (node (ref "R18") (pin "2") (pinfunction "2_2") (pintype "passive"))
      (node (ref "TR1") (pin "3") (pinfunction "3_3") (pintype "passive"))
    )
    (net (code "51") (name "Net-(C33-Pad2)") (class "Default")
      (node (ref "C33") (pin "2") (pinfunction "2_2") (pintype "passive"))
      (node (ref "R20") (pin "1") (pinfunction "1_1") (pintype "passive"))
    )
    (net (code "52") (name "Net-(C40-Pad1)") (class "Default")
      (node (ref "C40") (pin "1") (pinfunction "1_1") (pintype "passive"))
      (node (ref "D10") (pin "A") (pinfunction "A_A") (pintype "passive"))
      (node (ref "Q7") (pin "B") (pinfunction "B_B") (pintype "passive"))
      (node (ref "R42") (pin "2") (pinfunction "2_2") (pintype "passive"))
    )
    (net (code "53") (name "Net-(C40-Pad2)") (class "Default")
      (node (ref "C40") (pin "2") (pinfunction "2_2") (pintype "passive"))
      (node (ref "Q7") (pin "C") (pinfunction "C_C") (pintype "passive"))
      (node (ref "R36") (pin "2") (pinfunction "2_2") (pintype "passive"))
    )
    (net (code "54") (name "Net-(C41-Pad2)") (class "Default")
      (node (ref "C41") (pin "2") (pinfunction "2_2") (pintype "passive"))
      (node (ref "R44") (pin "1") (pinfunction "1_1") (pintype "passive"))
    )
    (net (code "55") (name "Net-(C42-Pad1)") (class "Default")
      (node (ref "C42") (pin "1") (pinfunction "1_1") (pintype "passive"))
      (node (ref "R47") (pin "1") (pinfunction "1_1") (pintype "passive"))
      (node (ref "R48") (pin "2") (pinfunction "2_2") (pintype "passive"))
    )
    (net (code "56") (name "Net-(C44-Pad1)") (class "Default")
      (node (ref "C44") (pin "1") (pinfunction "1_1") (pintype "passive"))
      (node (ref "R51") (pin "2") (pinfunction "2_2") (pintype "passive"))
    )
    (net (code "57") (name "Net-(C47-Pad2)") (class "Default")
      (node (ref "C47") (pin "2") (pinfunction "2_2") (pintype "passive"))
      (node (ref "R53") (pin "1") (pinfunction "1_1") (pintype "passive"))
    )
    (net (code "58") (name "Net-(C48-Pad1)") (class "Default")
      (node (ref "C48") (pin "1") (pinfunction "1_1") (pintype "passive"))
      (node (ref "R56") (pin "1") (pinfunction "1_1") (pintype "passive"))
      (node (ref "R57") (pin "2") (pinfunction "2_2") (pintype "passive"))
    )
    (net (code "59") (name "Net-(C55-Pad1)") (class "Default")
      (node (ref "C55") (pin "1") (pinfunction "1_1") (pintype "passive"))
      (node (ref "R63") (pin "1") (pinfunction "1_1") (pintype "passive"))
    )
    (net (code "60") (name "Net-(C61-Pad2)") (class "Default")
      (node (ref "C61") (pin "2") (pinfunction "2_2") (pintype "passive"))
      (node (ref "R66") (pin "1") (pinfunction "1_1") (pintype "passive"))
    )
    (net (code "61") (name "Net-(C90-Pad2)") (class "Default")
      (node (ref "C90") (pin "2") (pinfunction "2_2") (pintype "passive"))
      (node (ref "Q20") (pin "B") (pinfunction "B_B") (pintype "passive"))
      (node (ref "R104") (pin "1") (pinfunction "1_1") (pintype "passive"))
      (node (ref "R105") (pin "2") (pinfunction "2_2") (pintype "passive"))
      (node (ref "R106") (pin "2") (pinfunction "2_2") (pintype "passive"))
    )
    (net (code "62") (name "Net-(C91-Pad2)") (class "Default")
      (node (ref "C91") (pin "2") (pinfunction "2_2") (pintype "passive"))
      (node (ref "R109") (pin "2") (pinfunction "2_2") (pintype "passive"))
    )
    (net (code "63") (name "Net-(C98-Pad1)") (class "Default")
      (node (ref "C98") (pin "1") (pinfunction "1_1") (pintype "passive"))
      (node (ref "Q22") (pin "B") (pinfunction "B_B") (pintype "passive"))
      (node (ref "R110") (pin "1") (pinfunction "1_1") (pintype "passive"))
      (node (ref "R112") (pin "2") (pinfunction "2_2") (pintype "passive"))
    )
    (net (code "64") (name "Net-(D2-C)") (class "Default")
      (node (ref "C12") (pin "1") (pinfunction "1_1") (pintype "passive"))
      (node (ref "D2") (pin "3") (pinfunction "C_3") (pintype "passive"))
      (node (ref "L2") (pin "1") (pinfunction "1_1") (pintype "passive"))
      (node (ref "Q1") (pin "2") (pinfunction "D_2") (pintype "passive"))
    )
    (net (code "65") (name "Net-(D3-PadC)") (class "Default")
      (node (ref "D3") (pin "C") (pinfunction "C_C") (pintype "passive"))
      (node (ref "Q2") (pin "E") (pinfunction "E_E") (pintype "passive"))
      (node (ref "R6") (pin "2") (pinfunction "2_2") (pintype "passive"))
    )
    (net (code "66") (name "Net-(D4-PadC)") (class "Default")
      (node (ref "D4") (pin "C") (pinfunction "C_C") (pintype "passive"))
      (node (ref "TR1") (pin "2") (pinfunction "2_2") (pintype "passive"))
    )
    (net (code "67") (name "Net-(D18-PadA)") (class "Default")
      (node (ref "D18") (pin "A") (pinfunction "A_A") (pintype "passive"))
      (node (ref "Q14") (pin "B") (pinfunction "B_B") (pintype "passive"))
      (node (ref "R91") (pin "1") (pinfunction "1_1") (pintype "passive"))
      (node (ref "R96") (pin "2") (pinfunction "2_2") (pintype "passive"))
    )
    (net (code "68") (name "Net-(D18-PadC)") (class "Default")
      (node (ref "D18") (pin "C") (pinfunction "C_C") (pintype "passive"))
      (node (ref "D19") (pin "A") (pinfunction "A_A") (pintype "passive"))
    )
    (net (code "69") (name "Net-(FB1-1)") (class "Default")
      (node (ref "C34") (pin "1") (pinfunction "1_1") (pintype "passive"))
      (node (ref "D6") (pin "C") (pinfunction "C_C") (pintype "passive"))
      (node (ref "FB1") (pin "P$1") (pinfunction "1_P$1") (pintype "passive"))
      (node (ref "FB2") (pin "P$1") (pinfunction "1_P$1") (pintype "passive"))
      (node (ref "IC5") (pin "1") (pinfunction "VO_1") (pintype "passive"))
    )
    (net (code "70") (name "Net-(FB3-1)") (class "Default")
      (node (ref "C37") (pin "2") (pinfunction "2_2") (pintype "passive"))
      (node (ref "D7") (pin "A") (pinfunction "A_A") (pintype "passive"))
      (node (ref "FB3") (pin "P$1") (pinfunction "1_P$1") (pintype "passive"))
      (node (ref "IC6") (pin "1") (pinfunction "OUT_1") (pintype "passive"))
    )
    (net (code "71") (name "Net-(IC1-CAP)") (class "Default")
      (node (ref "C8") (pin "1") (pinfunction "1_1") (pintype "passive"))
      (node (ref "IC1") (pin "9") (pinfunction "CAP_9") (pintype "passive"))
    )
    (net (code "72") (name "Net-(IC1-GATE)") (class "Default")
      (node (ref "IC1") (pin "12") (pinfunction "GATE_12") (pintype "output"))
      (node (ref "Q1") (pin "1") (pinfunction "G_1") (pintype "passive"))
    )
    (net (code "73") (name "Net-(IC1-ITH)") (class "Default")
      (node (ref "C17") (pin "1") (pinfunction "1_1") (pintype "passive"))
      (node (ref "IC1") (pin "6") (pinfunction "ITH_6") (pintype "bidirectional"))
      (node (ref "R8") (pin "2") (pinfunction "2_2") (pintype "passive"))
    )
    (net (code "74") (name "Net-(IC1-RUN)") (class "Default")
      (node (ref "D1") (pin "C") (pinfunction "C_C") (pintype "passive"))
      (node (ref "IC1") (pin "8") (pinfunction "RUN_8") (pintype "input"))
      (node (ref "R2") (pin "2") (pinfunction "2_2") (pintype "passive"))
    )
    (net (code "75") (name "Net-(IC1-SENSE)") (class "Default")
      (node (ref "IC1") (pin "10") (pinfunction "SENSE_10") (pintype "input"))
      (node (ref "Q1") (pin "3") (pinfunction "S_3") (pintype "passive"))
      (node (ref "R3") (pin "2") (pinfunction "2_2") (pintype "passive"))
    )
    (net (code "76") (name "Net-(IC1-SS)") (class "Default")
      (node (ref "C9") (pin "2") (pinfunction "2_2") (pintype "passive"))
      (node (ref "IC1") (pin "4") (pinfunction "SS_4") (pintype "input"))
    )
    (net (code "77") (name "Net-(IC2-BOOT)") (class "Default")
      (node (ref "C24") (pin "2") (pinfunction "2_2") (pintype "passive"))
      (node (ref "IC2") (pin "1") (pinfunction "BOOT_1") (pintype "output"))
    )
    (net (code "78") (name "Net-(IC2-COMP)") (class "Default")
      (node (ref "C29") (pin "2") (pinfunction "2_2") (pintype "passive"))
      (node (ref "IC2") (pin "8") (pinfunction "COMP_8") (pintype "output"))
      (node (ref "R20") (pin "2") (pinfunction "2_2") (pintype "passive"))
    )
    (net (code "79") (name "Net-(IC2-EN)") (class "Default")
      (node (ref "IC2") (pin "3") (pinfunction "EN_3") (pintype "input"))
      (node (ref "R13") (pin "1") (pinfunction "1_1") (pintype "passive"))
      (node (ref "R16") (pin "2") (pinfunction "2_2") (pintype "passive"))
    )
    (net (code "80") (name "Net-(IC2-PH)") (class "Default")
      (node (ref "C24") (pin "1") (pinfunction "1_1") (pintype "passive"))
      (node (ref "C25") (pin "1") (pinfunction "1_1") (pintype "passive"))
      (node (ref "D5") (pin "C") (pinfunction "C_C") (pintype "passive"))
      (node (ref "IC2") (pin "10") (pinfunction "PH_10") (pintype "input"))
      (node (ref "TR1") (pin "1") (pinfunction "1_1") (pintype "passive"))
    )
    (net (code "81") (name "Net-(IC2-RT{slash}CLK)") (class "Default")
      (node (ref "IC2") (pin "5") (pinfunction "RT/CLK_5") (pintype "input"))
      (node (ref "R19") (pin "2") (pinfunction "2_2") (pintype "passive"))
    )
    (net (code "82") (name "Net-(IC2-SS{slash}TR)") (class "Default")
      (node (ref "C28") (pin "1") (pinfunction "1_1") (pintype "passive"))
      (node (ref "IC2") (pin "4") (pinfunction "SS/TR_4") (pintype "input"))
    )
    (net (code "83") (name "Net-(IC2-VSENSE)") (class "Default")
      (node (ref "IC2") (pin "7") (pinfunction "VSENSE_7") (pintype "input"))
      (node (ref "R18") (pin "1") (pinfunction "1_1") (pintype "passive"))
      (node (ref "R21") (pin "2") (pinfunction "2_2") (pintype "passive"))
    )
    (net (code "84") (name "Net-(IC3-B1)") (class "Default")
      (node (ref "IC3") (pin "14") (pinfunction "B1_14") (pintype "output"))
      (node (ref "RN2") (pin "1") (pinfunction "1_1") (pintype "passive"))
    )
    (net (code "85") (name "Net-(IC3-B4)") (class "Default")
      (node (ref "IC3") (pin "11") (pinfunction "B4_11") (pintype "input"))
      (node (ref "RN2") (pin "2") (pinfunction "1_2") (pintype "passive"))
    )
    (net (code "86") (name "Net-(IC4-Y0)") (class "Default")
      (node (ref "IC4") (pin "7") (pinfunction "Y0_7") (pintype "output"))
      (node (ref "RN1") (pin "1") (pinfunction "1_1") (pintype "passive"))
    )
    (net (code "87") (name "Net-(IC4-Y1)") (class "Default")
      (node (ref "IC4") (pin "6") (pinfunction "Y1_6") (pintype "output"))
      (node (ref "RN1") (pin "2") (pinfunction "1_2") (pintype "passive"))
    )
    (net (code "88") (name "Net-(IC4-Y2)") (class "Default")
      (node (ref "IC4") (pin "5") (pinfunction "Y2_5") (pintype "output"))
      (node (ref "RN1") (pin "3") (pinfunction "1_3") (pintype "passive"))
    )
    (net (code "89") (name "Net-(IC4-Y3)") (class "Default")
      (node (ref "IC4") (pin "3") (pinfunction "Y3_3") (pintype "output"))
      (node (ref "RN1") (pin "4") (pinfunction "1_4") (pintype "passive"))
    )
    (net (code "90") (name "Net-(IC7-B1)") (class "Default")
      (node (ref "IC7") (pin "14") (pinfunction "B1_14") (pintype "output"))
      (node (ref "RN2") (pin "3") (pinfunction "1_3") (pintype "passive"))
    )
    (net (code "91") (name "Net-(IC7-B2)") (class "Default")
      (node (ref "IC7") (pin "13") (pinfunction "B2_13") (pintype "output"))
      (node (ref "RN2") (pin "4") (pinfunction "1_4") (pintype "passive"))
    )
    (net (code "92") (name "Net-(IC9A-+IN)") (class "Default")
      (node (ref "IC9") (pin "3") (pinfunction "+IN_3") (pintype "input"))
      (node (ref "R44") (pin "2") (pinfunction "2_2") (pintype "passive"))
      (node (ref "R47") (pin "2") (pinfunction "2_2") (pintype "passive"))
    )
    (net (code "93") (name "Net-(IC9A--IN)") (class "Default")
      (node (ref "C46") (pin "1") (pinfunction "1_1") (pintype "passive"))
      (node (ref "IC9") (pin "2") (pinfunction "-IN_2") (pintype "input"))
      (node (ref "R51") (pin "1") (pinfunction "1_1") (pintype "passive"))
      (node (ref "R52") (pin "2") (pinfunction "2_2") (pintype "passive"))
      (node (ref "R53") (pin "2") (pinfunction "2_2") (pintype "passive"))
    )
    (net (code "94") (name "Net-(IC9B-+IN)") (class "Default")
      (node (ref "IC9") (pin "5") (pinfunction "+IN_5") (pintype "input"))
      (node (ref "R41") (pin "2") (pinfunction "2_2") (pintype "passive"))
      (node (ref "R45") (pin "1") (pinfunction "1_1") (pintype "passive"))
    )
    (net (code "95") (name "Net-(IC9B--IN)") (class "Default")
      (node (ref "C43") (pin "1") (pinfunction "1_1") (pintype "passive"))
      (node (ref "IC9") (pin "6") (pinfunction "-IN_6") (pintype "input"))
      (node (ref "R46") (pin "1") (pinfunction "1_1") (pintype "passive"))
      (node (ref "R50") (pin "2") (pinfunction "2_2") (pintype "passive"))
    )
    (net (code "96") (name "Net-(IC10A-+IN)") (class "Default")
      (node (ref "IC10") (pin "3") (pinfunction "+IN_3") (pintype "input"))
      (node (ref "R56") (pin "2") (pinfunction "2_2") (pintype "passive"))
    )
    (net (code "97") (name "Net-(IC10A--IN)") (class "Default")
      (node (ref "C60") (pin "1") (pinfunction "1_1") (pintype "passive"))
      (node (ref "IC10") (pin "2") (pinfunction "-IN_2") (pintype "input"))
      (node (ref "R62") (pin "2") (pinfunction "2_2") (pintype "passive"))
      (node (ref "R63") (pin "2") (pinfunction "2_2") (pintype "passive"))
      (node (ref "R66") (pin "2") (pinfunction "2_2") (pintype "passive"))
    )
    (net (code "98") (name "Net-(IC10B-+IN)") (class "Default")
      (node (ref "C39") (pin "1") (pinfunction "1_1") (pintype "passive"))
      (node (ref "IC10") (pin "5") (pinfunction "+IN_5") (pintype "input"))
      (node (ref "R31") (pin "2") (pinfunction "2_2") (pintype "passive"))
      (node (ref "R37") (pin "1") (pinfunction "1_1") (pintype "passive"))
    )
    (net (code "99") (name "Net-(IC12A-~{CLR})") (class "Default")
      (node (ref "D15") (pin "A") (pinfunction "A_A") (pintype "passive"))
      (node (ref "D16") (pin "A") (pinfunction "A_A") (pintype "passive"))
      (node (ref "IC12") (pin "6") (pinfunction "~{CLR}_6") (pintype "input"))
      (node (ref "R71") (pin "2") (pinfunction "2_2") (pintype "passive"))
    )
    (net (code "100") (name "Net-(IC13-~{RESET})") (class "Default")
      (node (ref "C63") (pin "1") (pinfunction "1_1") (pintype "passive"))
      (node (ref "IC13") (pin "18") (pinfunction "~{RESET}_18") (pintype "input"))
      (node (ref "JP1") (pin "2") (pinfunction "2_2") (pintype "passive"))
      (node (ref "R69") (pin "2") (pinfunction "2_2") (pintype "passive"))
    )
    (net (code "101") (name "Net-(IC14-TRIM{slash}NR)") (class "Default")
      (node (ref "C71") (pin "1") (pinfunction "1_1") (pintype "passive"))
      (node (ref "IC14") (pin "5") (pinfunction "TRIM/NR_5") (pintype "input"))
    )
    (net (code "102") (name "Net-(IC16-VOUTA)") (class "Default")
      (node (ref "IC16") (pin "4") (pinfunction "VOUTA_4") (pintype "output"))
      (node (ref "I_SET") (pin "1") (pinfunction "1_1") (pintype "passive"))
    )
    (net (code "103") (name "Net-(IC16-VOUTB)") (class "Default")
      (node (ref "IC16") (pin "3") (pinfunction "VOUTB_3") (pintype "output"))
      (node (ref "U_SET") (pin "1") (pinfunction "1_1") (pintype "passive"))
    )
    (net (code "104") (name "Net-(IC17-NO)") (class "Default")
      (node (ref "IC17") (pin "1") (pinfunction "NO_1") (pintype "bidirectional"))
      (node (ref "R75") (pin "1") (pinfunction "1_1") (pintype "passive"))
      (node (ref "ZD3") (pin "3") (pinfunction "C_3") (pintype "passive"))
    )
    (net (code "105") (name "Net-(IC18-AIN0{slash}REFP1)") (class "Default")
      (node (ref "C78") (pin "2") (pinfunction "2_2") (pintype "passive"))
      (node (ref "IC18") (pin "11") (pinfunction "AIN0/REFP1_11") (pintype "input"))
      (node (ref "R80") (pin "2") (pinfunction "2_2") (pintype "passive"))
    )
    (net (code "106") (name "Net-(IC18-AIN1)") (class "Default")
      (node (ref "C75") (pin "2") (pinfunction "2_2") (pintype "passive"))
      (node (ref "IC18") (pin "10") (pinfunction "AIN1_10") (pintype "input"))
      (node (ref "R77") (pin "2") (pinfunction "2_2") (pintype "passive"))
    )
    (net (code "107") (name "Net-(IC18-AIN2)") (class "Default")
      (node (ref "C76") (pin "2") (pinfunction "2_2") (pintype "passive"))
      (node (ref "IC18") (pin "7") (pinfunction "AIN2_7") (pintype "input"))
      (node (ref "R78") (pin "2") (pinfunction "2_2") (pintype "passive"))
    )
    (net (code "108") (name "Net-(IC18-AIN3{slash}REFN1)") (class "Default")
      (node (ref "C77") (pin "1") (pinfunction "1_1") (pintype "passive"))
      (node (ref "D17") (pin "C") (pinfunction "C_C") (pintype "passive"))
      (node (ref "IC18") (pin "6") (pinfunction "AIN3/REFN1_6") (pintype "input"))
      (node (ref "R81") (pin "2") (pinfunction "2_2") (pintype "passive"))
    )
    (net (code "109") (name "Net-(IC18-AVDD)") (class "Default")
      (node (ref "C81") (pin "2") (pinfunction "2_2") (pintype "passive"))
      (node (ref "C82") (pin "2") (pinfunction "2_2") (pintype "passive"))
      (node (ref "IC18") (pin "12") (pinfunction "AVDD_12") (pintype "power_in"))
      (node (ref "R82") (pin "2") (pinfunction "2_2") (pintype "passive"))
    )
    (net (code "110") (name "Net-(IC19A-+IN)") (class "Default")
      (node (ref "IC19") (pin "3") (pinfunction "+IN_3") (pintype "input"))
      (node (ref "IC19") (pin "5") (pinfunction "+IN_5") (pintype "input"))
      (node (ref "R94") (pin "1") (pinfunction "1_1") (pintype "passive"))
    )
    (net (code "111") (name "Net-(IC19A--IN)") (class "Default")
      (node (ref "IC19") (pin "2") (pinfunction "-IN_2") (pintype "input"))
      (node (ref "R86") (pin "2") (pinfunction "2_2") (pintype "passive"))
    )
    (net (code "112") (name "Net-(IC19A-OUT)") (class "Default")
      (node (ref "IC19") (pin "1") (pinfunction "OUT_1") (pintype "output"))
      (node (ref "R88") (pin "1") (pinfunction "1_1") (pintype "passive"))
    )
    (net (code "113") (name "Net-(IC19B--IN)") (class "Default")
      (node (ref "IC19") (pin "6") (pinfunction "-IN_6") (pintype "input"))
      (node (ref "R99") (pin "2") (pinfunction "2_2") (pintype "passive"))
    )
    (net (code "114") (name "Net-(IC19B-OUT)") (class "Default")
      (node (ref "IC19") (pin "7") (pinfunction "OUT_7") (pintype "output"))
      (node (ref "R100") (pin "1") (pinfunction "1_1") (pintype "passive"))
    )
    (net (code "115") (name "Net-(IC20-+IN)") (class "Default")
      (node (ref "C86") (pin "2") (pinfunction "2_2") (pintype "passive"))
      (node (ref "C87") (pin "1") (pinfunction "1_1") (pintype "passive"))
      (node (ref "IC20") (pin "2") (pinfunction "+IN_2") (pintype "input"))
      (node (ref "R83") (pin "2") (pinfunction "2_2") (pintype "passive"))
      (node (ref "R89") (pin "1") (pinfunction "1_1") (pintype "passive"))
    )
    (net (code "116") (name "Net-(IC20--IN)") (class "Default")
      (node (ref "C87") (pin "2") (pinfunction "2_2") (pintype "passive"))
      (node (ref "IC20") (pin "3") (pinfunction "-IN_3") (pintype "input"))
      (node (ref "R95") (pin "2") (pinfunction "2_2") (pintype "passive"))
    )
    (net (code "117") (name "Net-(IC20-OUT)") (class "Default")
      (node (ref "IC20") (pin "7") (pinfunction "OUT_7") (pintype "output"))
      (node (ref "Q17") (pin "1") (pinfunction "G_1") (pintype "passive"))
      (node (ref "R101") (pin "2") (pinfunction "2_2") (pintype "passive"))
      (node (ref "R91") (pin "2") (pinfunction "2_2") (pintype "passive"))
    )
    (net (code "118") (name "Net-(K1A--)") (class "Default")
      (node (ref "D20") (pin "A") (pinfunction "A_A") (pintype "passive"))
      (node (ref "K1") (pin "8") (pinfunction "-_8") (pintype "passive"))
      (node (ref "Q23") (pin "3") (pinfunction "D_3") (pintype "passive"))
      (node (ref "R113") (pin "1") (pinfunction "1_1") (pintype "passive"))
    )
    (net (code "119") (name "Net-(K1B-S)") (class "Default")
      (node (ref "K1") (pin "4") (pinfunction "S_4") (pintype "passive"))
      (node (ref "X3") (pin "4") (pinfunction "1_4") (pintype "passive"))
    )
    (net (code "120") (name "Net-(K1C-S)") (class "Default")
      (node (ref "K1") (pin "5") (pinfunction "S_5") (pintype "passive"))
      (node (ref "X3") (pin "5") (pinfunction "1_5") (pintype "passive"))
    )
    (net (code "121") (name "Net-(LED1-C)") (class "Default")
      (node (ref "LED1") (pin "CC") (pinfunction "C_CC") (pintype "passive"))
      (node (ref "R73") (pin "1") (pinfunction "1_1") (pintype "passive"))
    )
    (net (code "122") (name "Net-(LED2A-C)") (class "Default")
      (node (ref "LED2") (pin "BC") (pinfunction "C_BC") (pintype "passive"))
      (node (ref "R79") (pin "2") (pinfunction "2_2") (pintype "passive"))
    )
    (net (code "123") (name "Net-(LED2B-C)") (class "Default")
      (node (ref "LED2") (pin "TC") (pinfunction "C_TC") (pintype "passive"))
      (node (ref "R113") (pin "2") (pinfunction "2_2") (pintype "passive"))
    )
    (net (code "124") (name "Net-(LED3A-C)") (class "Default")
      (node (ref "LED3") (pin "BC") (pinfunction "C_BC") (pintype "passive"))
      (node (ref "R92") (pin "2") (pinfunction "2_2") (pintype "passive"))
    )
    (net (code "125") (name "Net-(LED3B-C)") (class "Default")
      (node (ref "LED3") (pin "TC") (pinfunction "C_TC") (pintype "passive"))
      (node (ref "R90") (pin "1") (pinfunction "1_1") (pintype "passive"))
    )
    (net (code "126") (name "Net-(Q3-B)") (class "Default")
      (node (ref "Q3") (pin "1") (pinfunction "B_1") (pintype "passive"))
      (node (ref "R34") (pin "2") (pinfunction "2_2") (pintype "passive"))
    )
    (net (code "127") (name "Net-(Q3-E)") (class "Default")
      (node (ref "Q3") (pin "3") (pinfunction "E_3") (pintype "passive"))
      (node (ref "R25") (pin "2") (pinfunction "2_2") (pintype "passive"))
    )
    (net (code "128") (name "Net-(Q4-B)") (class "Default")
      (node (ref "Q4") (pin "1") (pinfunction "B_1") (pintype "passive"))
      (node (ref "R35") (pin "2") (pinfunction "2_2") (pintype "passive"))
    )
    (net (code "129") (name "Net-(Q4-E)") (class "Default")
      (node (ref "Q4") (pin "3") (pinfunction "E_3") (pintype "passive"))
      (node (ref "R26") (pin "2") (pinfunction "2_2") (pintype "passive"))
    )
    (net (code "130") (name "Net-(Q5-G)") (class "Default")
      (node (ref "Q5") (pin "1") (pinfunction "G_1") (pintype "passive"))
      (node (ref "Q6") (pin "2") (pinfunction "C_2") (pintype "passive"))
      (node (ref "Q6") (pin "4") (pinfunction "C_4") (pintype "passive"))
      (node (ref "R30") (pin "2") (pinfunction "2_2") (pintype "passive"))
      (node (ref "ZD2") (pin "A") (pinfunction "A_A") (pintype "passive"))
    )
    (net (code "131") (name "Net-(Q5-S)") (class "Default")
      (node (ref "Q5") (pin "3") (pinfunction "S_3") (pintype "passive"))
      (node (ref "R29") (pin "1") (pinfunction "1_1") (pintype "passive"))
    )
    (net (code "132") (name "Net-(Q6-B)") (class "Default")
      (node (ref "Q6") (pin "1") (pinfunction "B_1") (pintype "passive"))
      (node (ref "R36") (pin "1") (pinfunction "1_1") (pintype "passive"))
      (node (ref "R38") (pin "1") (pinfunction "1_1") (pintype "passive"))
    )
    (net (code "133") (name "Net-(Q6-E)") (class "Default")
      (node (ref "Q6") (pin "3") (pinfunction "E_3") (pintype "passive"))
      (node (ref "R39") (pin "1") (pinfunction "1_1") (pintype "passive"))
    )
    (net (code "134") (name "Net-(Q8-B)") (class "Default")
      (node (ref "D11") (pin "C") (pinfunction "C_C") (pintype "passive"))
      (node (ref "Q8") (pin "1") (pinfunction "B_1") (pintype "passive"))
      (node (ref "R43") (pin "2") (pinfunction "2_2") (pintype "passive"))
    )
    (net (code "135") (name "Net-(Q8-C-Pad2)") (class "Default")
      (node (ref "Q8") (pin "2") (pinfunction "C_2") (pintype "passive"))
      (node (ref "Q8") (pin "4") (pinfunction "C_4") (pintype "passive"))
      (node (ref "R33") (pin "1") (pinfunction "1_1") (pintype "passive"))
      (node (ref "R34") (pin "1") (pinfunction "1_1") (pintype "passive"))
      (node (ref "R35") (pin "1") (pinfunction "1_1") (pintype "passive"))
    )
    (net (code "136") (name "Net-(Q8-E)") (class "Default")
      (node (ref "D11") (pin "A") (pinfunction "A_A") (pintype "passive"))
      (node (ref "Q8") (pin "3") (pinfunction "E_3") (pintype "passive"))
      (node (ref "R49") (pin "2") (pinfunction "2_2") (pintype "passive"))
    )
    (net (code "137") (name "Net-(Q9-D)") (class "Default")
      (node (ref "C45") (pin "2") (pinfunction "2_2") (pintype "passive"))
      (node (ref "Q9") (pin "3") (pinfunction "D_3") (pintype "passive"))
      (node (ref "R49") (pin "1") (pinfunction "1_1") (pintype "passive"))
    )
    (net (code "138") (name "Net-(Q9-G)") (class "Default")
      (node (ref "C45") (pin "1") (pinfunction "1_1") (pintype "passive"))
      (node (ref "Q9") (pin "1") (pinfunction "G_1") (pintype "passive"))
      (node (ref "R54") (pin "1") (pinfunction "1_1") (pintype "passive"))
      (node (ref "R55") (pin "2") (pinfunction "2_2") (pintype "passive"))
    )
    (net (code "139") (name "Net-(Q10-S-Pad1)") (class "Default")
      (node (ref "Q10") (pin "1") (pinfunction "S_1") (pintype "passive"))
      (node (ref "Q10") (pin "2") (pinfunction "S_2") (pintype "passive"))
      (node (ref "Q10") (pin "3") (pinfunction "S_3") (pintype "passive"))
      (node (ref "R59") (pin "1") (pinfunction "1_1") (pintype "passive"))
      (node (ref "R61") (pin "1") (pinfunction "1_1") (pintype "passive"))
    )
    (net (code "140") (name "Net-(Q11-S-Pad1)") (class "Default")
      (node (ref "Q11") (pin "1") (pinfunction "S_1") (pintype "passive"))
      (node (ref "Q11") (pin "2") (pinfunction "S_2") (pintype "passive"))
      (node (ref "Q11") (pin "3") (pinfunction "S_3") (pintype "passive"))
      (node (ref "R67") (pin "2") (pinfunction "2_2") (pintype "passive"))
    )
    (net (code "141") (name "Net-(Q12-D)") (class "Default")
      (node (ref "Q12") (pin "3") (pinfunction "D_3") (pintype "passive"))
      (node (ref "R74") (pin "2") (pinfunction "2_2") (pintype "passive"))
    )
    (net (code "142") (name "Net-(Q13-PadA2)") (class "Default")
      (node (ref "Q13") (pin "A2") (pinfunction "A2_A2") (pintype "passive"))
      (node (ref "R93") (pin "2") (pinfunction "2_2") (pintype "passive"))
    )
    (net (code "143") (name "Net-(Q13-PadG)") (class "Default")
      (node (ref "Q13") (pin "G") (pinfunction "G_G") (pintype "passive"))
      (node (ref "Q14") (pin "C") (pinfunction "C_C") (pintype "passive"))
      (node (ref "R85") (pin "1") (pinfunction "1_1") (pintype "passive"))
    )
    (net (code "144") (name "Net-(Q14-PadE)") (class "Default")
      (node (ref "Q14") (pin "E") (pinfunction "E_E") (pintype "passive"))
      (node (ref "R97") (pin "2") (pinfunction "2_2") (pintype "passive"))
    )
    (net (code "145") (name "Net-(Q15-D)") (class "Default")
      (node (ref "Q15") (pin "3") (pinfunction "D_3") (pintype "passive"))
      (node (ref "R90") (pin "2") (pinfunction "2_2") (pintype "passive"))
    )
    (net (code "146") (name "Net-(Q16-D)") (class "Default")
      (node (ref "Q16") (pin "3") (pinfunction "D_3") (pintype "passive"))
      (node (ref "R92") (pin "1") (pinfunction "1_1") (pintype "passive"))
    )
    (net (code "147") (name "Net-(Q18-G)") (class "Default")
      (node (ref "Q18") (pin "4") (pinfunction "G_4") (pintype "passive"))
      (node (ref "Q19") (pin "C") (pinfunction "C_C") (pintype "passive"))
      (node (ref "R101") (pin "1") (pinfunction "1_1") (pintype "passive"))
    )
    (net (code "148") (name "Net-(Q19-PadB)") (class "Default")
      (node (ref "Q19") (pin "B") (pinfunction "B_B") (pintype "passive"))
      (node (ref "R102") (pin "1") (pinfunction "1_1") (pintype "passive"))
      (node (ref "R103") (pin "2") (pinfunction "2_2") (pintype "passive"))
    )
    (net (code "149") (name "Net-(Q20-PadC)") (class "Default")
      (node (ref "Q20") (pin "C") (pinfunction "C_C") (pintype "passive"))
      (node (ref "R108") (pin "2") (pinfunction "2_2") (pintype "passive"))
    )
    (net (code "150") (name "Net-(Q21-PadB)") (class "Default")
      (node (ref "Q21") (pin "B") (pinfunction "B_B") (pintype "passive"))
      (node (ref "R108") (pin "1") (pinfunction "1_1") (pintype "passive"))
      (node (ref "R111") (pin "2") (pinfunction "2_2") (pintype "passive"))
    )
    (net (code "151") (name "Net-(Q22-PadC)") (class "Default")
      (node (ref "Q22") (pin "C") (pinfunction "C_C") (pintype "passive"))
      (node (ref "R106") (pin "1") (pinfunction "1_1") (pintype "passive"))
    )
    (net (code "152") (name "Net-(R27-Pad1)") (class "Default")
      (node (ref "R27") (pin "1") (pinfunction "1_1") (pintype "passive"))
      (node (ref "R32") (pin "2") (pinfunction "2_2") (pintype "passive"))
    )
    (net (code "153") (name "Net-(R61-Pad2)") (class "Default")
      (node (ref "R61") (pin "2") (pinfunction "2_2") (pintype "passive"))
      (node (ref "R67") (pin "2S") (pinfunction "2S_2S") (pintype "passive"))
    )
    (net (code "154") (name "Net-(R67-Pad1S)") (class "Default")
      (node (ref "R67") (pin "1S") (pinfunction "1S_1S") (pintype "passive"))
      (node (ref "R68") (pin "1") (pinfunction "1_1") (pintype "passive"))
    )
    (net (code "155") (name "Net-(R75-Pad2)") (class "Default")
      (node (ref "R75") (pin "2") (pinfunction "2_2") (pintype "passive"))
      (node (ref "R76") (pin "1") (pinfunction "1_1") (pintype "passive"))
    )
    (net (code "156") (name "Net-(R76-Pad2)") (class "Default")
      (node (ref "R76") (pin "2") (pinfunction "2_2") (pintype "passive"))
      (node (ref "X3") (pin "1") (pinfunction "1_1") (pintype "passive"))
    )
    (net (code "157") (name "Net-(R102-Pad2)") (class "Default")
      (node (ref "R102") (pin "2") (pinfunction "2_2") (pintype "passive"))
      (node (ref "ZD4") (pin "A") (pinfunction "A_A") (pintype "passive"))
    )
    (net (code "158") (name "Net-(X4B-1)") (class "Default")
      (node (ref "F2") (pin "2") (pinfunction "2_2") (pintype "passive"))
      (node (ref "X4") (pin "10") (pinfunction "1_10") (pintype "passive"))
      (node (ref "X4") (pin "6") (pinfunction "1_6") (pintype "passive"))
      (node (ref "X4") (pin "7") (pinfunction "1_7") (pintype "passive"))
      (node (ref "X4") (pin "8") (pinfunction "1_8") (pintype "passive"))
      (node (ref "X4") (pin "9") (pinfunction "1_9") (pintype "passive"))
    )
    (net (code "159") (name "OE") (class "Default")
      (node (ref "IC13") (pin "2") (pinfunction "GPB1_2") (pintype "bidirectional"))
      (node (ref "OE") (pin "1") (pinfunction "1_1") (pintype "passive"))
    )
    (net (code "160") (name "OE_GREEN") (class "Default")
      (node (ref "IC13") (pin "7") (pinfunction "GPB6_7") (pintype "bidirectional"))
      (node (ref "LED1") (pin "GREEN") (pinfunction "AG_GREEN") (pintype "passive"))
    )
    (net (code "161") (name "OE_RED") (class "Default")
      (node (ref "IC13") (pin "8") (pinfunction "GPB7_8") (pintype "bidirectional"))
      (node (ref "LED1") (pin "RED") (pinfunction "AR_RED") (pintype "passive"))
    )
    (net (code "162") (name "OE_SYNC") (class "Default")
      (node (ref "IC7") (pin "4") (pinfunction "A2_4") (pintype "input"))
      (node (ref "X2") (pin "6") (pinfunction "1_6") (pintype "passive"))
    )
    (net (code "163") (name "OE_TRIG") (class "Default")
      (node (ref "IC12") (pin "1") (pinfunction "CLK_1") (pintype "input"))
      (node (ref "RN2") (pin "5") (pinfunction "2_5") (pintype "passive"))
    )
    (net (code "164") (name "OUTC+") (class "Default")
      (node (ref "C93") (pin "1") (pinfunction "1_1") (pintype "passive"))
      (node (ref "C94") (pin "+") (pinfunction "+_+") (pintype "passive"))
      (node (ref "C95") (pin "1") (pinfunction "1_1") (pintype "passive"))
      (node (ref "C96") (pin "1") (pinfunction "1_1") (pintype "passive"))
      (node (ref "J2") (pin "1") (pinfunction "1_1") (pintype "passive"))
      (node (ref "J2") (pin "NC1") (pinfunction "1_NC1") (pintype "passive"))
      (node (ref "J2") (pin "NC2") (pinfunction "1_NC2") (pintype "passive"))
      (node (ref "J2") (pin "NC3") (pinfunction "1_NC3") (pintype "passive"))
      (node (ref "J2") (pin "NC4") (pinfunction "1_NC4") (pintype "passive"))
      (node (ref "X4") (pin "1") (pinfunction "1_1") (pintype "passive"))
      (node (ref "X4") (pin "2") (pinfunction "1_2") (pintype "passive"))
      (node (ref "X4") (pin "3") (pinfunction "1_3") (pintype "passive"))
      (node (ref "X4") (pin "4") (pinfunction "1_4") (pintype "passive"))
      (node (ref "X4") (pin "5") (pinfunction "1_5") (pintype "passive"))
    )
    (net (code "165") (name "OUTC-") (class "Default")
      (node (ref "C94") (pin "-") (pinfunction "-_-") (pintype "passive"))
      (node (ref "C95") (pin "2") (pinfunction "2_2") (pintype "passive"))
      (node (ref "C96") (pin "2") (pinfunction "2_2") (pintype "passive"))
      (node (ref "C97") (pin "2") (pinfunction "2_2") (pintype "passive"))
      (node (ref "J3") (pin "1") (pinfunction "1_1") (pintype "passive"))
      (node (ref "J3") (pin "NC1") (pinfunction "1_NC1") (pintype "passive"))
      (node (ref "J3") (pin "NC2") (pinfunction "1_NC2") (pintype "passive"))
      (node (ref "J3") (pin "NC3") (pinfunction "1_NC3") (pintype "passive"))
      (node (ref "J3") (pin "NC4") (pinfunction "1_NC4") (pintype "passive"))
      (node (ref "X4") (pin "16") (pinfunction "1_16") (pintype "passive"))
      (node (ref "X4") (pin "17") (pinfunction "1_17") (pintype "passive"))
      (node (ref "X4") (pin "18") (pinfunction "1_18") (pintype "passive"))
      (node (ref "X4") (pin "19") (pinfunction "1_19") (pintype "passive"))
      (node (ref "X4") (pin "20") (pinfunction "1_20") (pintype "passive"))
    )
    (net (code "166") (name "OVP_EN") (class "Default")
      (node (ref "IC13") (pin "5") (pinfunction "GPB4_5") (pintype "bidirectional"))
      (node (ref "IC20") (pin "6") (pinfunction "~{SHDN}_6") (pintype "input"))
      (node (ref "R87") (pin "2") (pinfunction "2_2") (pintype "passive"))
    )
    (net (code "167") (name "PE") (class "Default")
      (node (ref "C3") (pin "2") (pinfunction "2_2") (pintype "passive"))
      (node (ref "C4") (pin "1") (pinfunction "1_1") (pintype "passive"))
      (node (ref "C93") (pin "2") (pinfunction "2_2") (pintype "passive"))
      (node (ref "C97") (pin "1") (pinfunction "1_1") (pintype "passive"))
      (node (ref "J1") (pin "1") (pinfunction "P$1_1") (pintype "bidirectional"))
      (node (ref "J1") (pin "2") (pinfunction "P$1_2") (pintype "bidirectional"))
      (node (ref "X3") (pin "3") (pinfunction "1_3") (pintype "passive"))
    )
    (net (code "168") (name "POST_OE") (class "Default")
      (node (ref "IC12") (pin "5") (pinfunction "Q_5") (pintype "output"))
      (node (ref "R54") (pin "2") (pinfunction "2_2") (pintype "passive"))
    )
    (net (code "169") (name "POST_OUT+") (class "Default")
      (node (ref "C47") (pin "1") (pinfunction "1_1") (pintype "passive"))
      (node (ref "C61") (pin "1") (pinfunction "1_1") (pintype "passive"))
      (node (ref "D8") (pin "A") (pinfunction "A_A") (pintype "passive"))
      (node (ref "F1") (pin "1") (pinfunction "1_1") (pintype "passive"))
      (node (ref "Q3") (pin "2") (pinfunction "C_2") (pintype "passive"))
      (node (ref "Q4") (pin "2") (pinfunction "C_2") (pintype "passive"))
      (node (ref "R10") (pin "2") (pinfunction "2_2") (pintype "passive"))
      (node (ref "R27") (pin "2") (pinfunction "2_2") (pintype "passive"))
      (node (ref "R28") (pin "2") (pinfunction "2_2") (pintype "passive"))
      (node (ref "R29") (pin "2") (pinfunction "2_2") (pintype "passive"))
      (node (ref "R30") (pin "1") (pinfunction "1_1") (pintype "passive"))
      (node (ref "ZD2") (pin "C") (pinfunction "C_C") (pintype "passive"))
    )
    (net (code "170") (name "POST_OUT-") (class "Default")
      (node (ref "C41") (pin "1") (pinfunction "1_1") (pintype "passive"))
      (node (ref "C92") (pin "-") (pinfunction "-_-") (pintype "passive"))
      (node (ref "C98") (pin "2") (pinfunction "2_2") (pintype "passive"))
      (node (ref "D14") (pin "A") (pinfunction "A_A") (pintype "passive"))
      (node (ref "JP4") (pin "1") (pinfunction "1_1") (pintype "passive"))
      (node (ref "K1") (pin "7") (pinfunction "O_7") (pintype "passive"))
      (node (ref "Q10") (pin "MB") (pinfunction "D_MB") (pintype "passive"))
      (node (ref "Q11") (pin "MB") (pinfunction "D_MB") (pintype "passive"))
      (node (ref "Q22") (pin "E") (pinfunction "E_E") (pintype "passive"))
      (node (ref "R109") (pin "1") (pinfunction "1_1") (pintype "passive"))
      (node (ref "R112") (pin "1") (pinfunction "1_1") (pintype "passive"))
      (node (ref "X4") (pin "11") (pinfunction "1_11") (pintype "passive"))
      (node (ref "X4") (pin "12") (pinfunction "1_12") (pintype "passive"))
      (node (ref "X4") (pin "13") (pinfunction "1_13") (pintype "passive"))
      (node (ref "X4") (pin "14") (pinfunction "1_14") (pintype "passive"))
      (node (ref "X4") (pin "15") (pinfunction "1_15") (pintype "passive"))
      (node (ref "ZD5") (pin "A") (pinfunction "A_A") (pintype "passive"))
    )
    (net (code "171") (name "POST_OUTF+") (class "Default")
      (node (ref "C90") (pin "1") (pinfunction "1_1") (pintype "passive"))
      (node (ref "C91") (pin "1") (pinfunction "1_1") (pintype "passive"))
      (node (ref "C92") (pin "+") (pinfunction "+_+") (pintype "passive"))
      (node (ref "F1") (pin "2") (pinfunction "2_2") (pintype "passive"))
      (node (ref "F2") (pin "1") (pinfunction "1_1") (pintype "passive"))
      (node (ref "JP3") (pin "2") (pinfunction "2_2") (pintype "passive"))
      (node (ref "K1") (pin "2") (pinfunction "O_2") (pintype "passive"))
      (node (ref "Q13") (pin "A1") (pinfunction "A1_A1") (pintype "passive"))
      (node (ref "Q18") (pin "MB") (pinfunction "D_MB") (pintype "passive"))
      (node (ref "Q20") (pin "E") (pinfunction "E_E") (pintype "passive"))
      (node (ref "R104") (pin "2") (pinfunction "2_2") (pintype "passive"))
      (node (ref "R85") (pin "2") (pinfunction "2_2") (pintype "passive"))
      (node (ref "ZD4") (pin "C") (pinfunction "C_C") (pintype "passive"))
      (node (ref "ZD5") (pin "C") (pinfunction "C_C") (pintype "passive"))
    )
    (net (code "172") (name "PREG_IN-") (class "Default")
      (node (ref "C10") (pin "2") (pinfunction "2_2") (pintype "passive"))
      (node (ref "C11") (pin "-") (pinfunction "-_-") (pintype "passive"))
      (node (ref "C15") (pin "2") (pinfunction "2_2") (pintype "passive"))
      (node (ref "C16") (pin "-") (pinfunction "-_-") (pintype "passive"))
      (node (ref "C2") (pin "-") (pinfunction "-_-") (pintype "passive"))
      (node (ref "C3") (pin "1") (pinfunction "1_1") (pintype "passive"))
      (node (ref "C5") (pin "2") (pinfunction "2_2") (pintype "passive"))
      (node (ref "C6") (pin "2") (pinfunction "2_2") (pintype "passive"))
      (node (ref "C7") (pin "2") (pinfunction "2_2") (pintype "passive"))
      (node (ref "D2") (pin "1") (pinfunction "A_1") (pintype "passive"))
      (node (ref "D2") (pin "2") (pinfunction "A_2") (pintype "passive"))
      (node (ref "IC1") (pin "TP") (pinfunction "PGND_TP") (pintype "passive"))
      (node (ref "L1") (pin "4") (pinfunction "2_4") (pintype "passive"))
      (node (ref "R2") (pin "1") (pinfunction "1_1") (pintype "passive"))
      (node (ref "R5") (pin "1") (pinfunction "1_1") (pintype "passive"))
      (node (ref "SH1") (pin "1") (pinfunction "GND_A_1") (pintype "bidirectional"))
      (node (ref "SH2") (pin "2") (pinfunction "GND_B_2") (pintype "bidirectional"))
      (node (ref "SH3") (pin "2") (pinfunction "GND_B_2") (pintype "bidirectional"))
      (node (ref "ZD1") (pin "A") (pinfunction "A_A") (pintype "passive"))
    )
    (net (code "173") (name "PREG_OUT+") (class "Default")
      (node (ref "C13") (pin "+") (pinfunction "+_+") (pintype "passive"))
      (node (ref "C14") (pin "1") (pinfunction "1_1") (pintype "passive"))
      (node (ref "D8") (pin "C") (pinfunction "C_C") (pintype "passive"))
      (node (ref "L3") (pin "2") (pinfunction "2_2") (pintype "passive"))
      (node (ref "R25") (pin "1") (pinfunction "1_1") (pintype "passive"))
      (node (ref "R26") (pin "1") (pinfunction "1_1") (pintype "passive"))
      (node (ref "R33") (pin "2") (pinfunction "2_2") (pintype "passive"))
      (node (ref "R4") (pin "2") (pinfunction "2_2") (pintype "passive"))
    )
    (net (code "174") (name "PREG_OUT-") (class "Default")
      (node (ref "C13") (pin "-") (pinfunction "-_-") (pintype "passive"))
      (node (ref "C14") (pin "2") (pinfunction "2_2") (pintype "passive"))
      (node (ref "D14") (pin "C") (pinfunction "C_C") (pintype "passive"))
      (node (ref "Q18") (pin "1") (pinfunction "S_1") (pintype "passive"))
      (node (ref "Q18") (pin "2") (pinfunction "S_2") (pintype "passive"))
      (node (ref "Q18") (pin "3") (pinfunction "S_3") (pintype "passive"))
      (node (ref "Q19") (pin "E") (pinfunction "E_E") (pintype "passive"))
      (node (ref "Q5") (pin "2") (pinfunction "D_2") (pintype "passive"))
      (node (ref "R103") (pin "1") (pinfunction "1_1") (pintype "passive"))
      (node (ref "R32") (pin "1") (pinfunction "1_1") (pintype "passive"))
      (node (ref "R67") (pin "1") (pinfunction "1_1") (pintype "passive"))
      (node (ref "R93") (pin "1") (pinfunction "1_1") (pintype "passive"))
      (node (ref "SH2") (pin "1") (pinfunction "GND_A_1") (pintype "bidirectional"))
    )
    (net (code "175") (name "PRE_OE") (class "Default")
      (node (ref "D1") (pin "A") (pinfunction "A_A") (pintype "passive"))
      (node (ref "IC12") (pin "2") (pinfunction "D_2") (pintype "input"))
      (node (ref "OE") (pin "2") (pinfunction "2_2") (pintype "passive"))
    )
    (net (code "176") (name "PWRGOOD") (class "Default")
      (node (ref "D16") (pin "C") (pinfunction "C_C") (pintype "passive"))
      (node (ref "IC13") (pin "24") (pinfunction "GPA3_24") (pintype "bidirectional"))
      (node (ref "IC2") (pin "6") (pinfunction "PWRGD_6") (pintype "output"))
      (node (ref "R17") (pin "2") (pinfunction "2_2") (pintype "passive"))
    )
    (net (code "177") (name "RSENSE") (class "Default")
      (node (ref "IC13") (pin "3") (pinfunction "GPB2_3") (pintype "bidirectional"))
      (node (ref "Q23") (pin "1") (pinfunction "G_1") (pintype "passive"))
      (node (ref "R114") (pin "2") (pinfunction "2_2") (pintype "passive"))
    )
    (net (code "178") (name "SCLK") (class "Default")
      (node (ref "IC13") (pin "12") (pinfunction "SCK_12") (pintype "input"))
      (node (ref "IC15") (pin "3") (pinfunction "SCLK_3") (pintype "input"))
      (node (ref "IC16") (pin "6") (pinfunction "SCLK_6") (pintype "input"))
      (node (ref "IC18") (pin "1") (pinfunction "SCLK_1") (pintype "input"))
      (node (ref "RN2") (pin "8") (pinfunction "2_8") (pintype "passive"))
    )
    (net (code "179") (name "SENSE+") (class "Default")
      (node (ref "JP3") (pin "1") (pinfunction "1_1") (pintype "passive"))
      (node (ref "K1") (pin "3") (pinfunction "P_3") (pintype "passive"))
      (node (ref "R105") (pin "1") (pinfunction "1_1") (pintype "passive"))
      (node (ref "R45") (pin "2") (pinfunction "2_2") (pintype "passive"))
    )
    (net (code "180") (name "SENSE-") (class "Default")
      (node (ref "JP4") (pin "2") (pinfunction "2_2") (pintype "passive"))
      (node (ref "K1") (pin "6") (pinfunction "P_6") (pintype "passive"))
      (node (ref "R110") (pin "2") (pinfunction "2_2") (pintype "passive"))
      (node (ref "R46") (pin "2") (pinfunction "2_2") (pintype "passive"))
    )
    (net (code "181") (name "SENSE_ERR") (class "Default")
      (node (ref "IC13") (pin "21") (pinfunction "GPA0_21") (pintype "bidirectional"))
      (node (ref "Q21") (pin "C") (pinfunction "C_C") (pintype "passive"))
      (node (ref "R107") (pin "1") (pinfunction "1_1") (pintype "passive"))
    )
    (net (code "182") (name "SGND") (class "Default")
      (node (ref "C17") (pin "2") (pinfunction "2_2") (pintype "passive"))
      (node (ref "C18") (pin "2") (pinfunction "2_2") (pintype "passive"))
      (node (ref "C9") (pin "1") (pinfunction "1_1") (pintype "passive"))
      (node (ref "IC1") (pin "1") (pinfunction "PLLIN/MODE_1") (pintype "input"))
      (node (ref "IC1") (pin "2") (pinfunction "FREQ_2") (pintype "input"))
      (node (ref "IC1") (pin "3") (pinfunction "SGND_3") (pintype "passive"))
      (node (ref "R11") (pin "2") (pinfunction "2_2") (pintype "passive"))
      (node (ref "SH3") (pin "1") (pinfunction "GND_A_1") (pintype "bidirectional"))
    )
    (net (code "183") (name "TEMP_CS") (class "Default")
      (node (ref "IC15") (pin "1") (pinfunction "~{CS}_1") (pintype "input"))
      (node (ref "RN1") (pin "5") (pinfunction "2_5") (pintype "passive"))
    )
    (net (code "184") (name "U_MON") (class "Default")
      (node (ref "C43") (pin "2") (pinfunction "2_2") (pintype "passive"))
      (node (ref "IC9") (pin "7") (pinfunction "OUT_7") (pintype "output"))
      (node (ref "R50") (pin "1") (pinfunction "1_1") (pintype "passive"))
      (node (ref "R52") (pin "1") (pinfunction "1_1") (pintype "passive"))
      (node (ref "R80") (pin "1") (pinfunction "1_1") (pintype "passive"))
      (node (ref "R83") (pin "1") (pinfunction "1_1") (pintype "passive"))
    )
    (net (code "185") (name "U_SERVO") (class "Default")
      (node (ref "C44") (pin "2") (pinfunction "2_2") (pintype "passive"))
      (node (ref "C46") (pin "2") (pinfunction "2_2") (pintype "passive"))
      (node (ref "D12") (pin "C") (pinfunction "C_C") (pintype "passive"))
      (node (ref "IC9") (pin "1") (pinfunction "OUT_1") (pintype "output"))
      (node (ref "R42") (pin "1") (pinfunction "1_1") (pintype "passive"))
      (node (ref "R86") (pin "1") (pinfunction "1_1") (pintype "passive"))
    )
    (net (code "186") (name "U_SET") (class "Default")
      (node (ref "IC17") (pin "3") (pinfunction "NC_3") (pintype "bidirectional"))
      (node (ref "JP2") (pin "1") (pinfunction "1_1") (pintype "passive"))
      (node (ref "R78") (pin "1") (pinfunction "1_1") (pintype "passive"))
      (node (ref "U_SET") (pin "2") (pinfunction "2_2") (pintype "passive"))
    )
    (net (code "187") (name "U_SET_OUT") (class "Default")
      (node (ref "IC17") (pin "4") (pinfunction "COM_4") (pintype "bidirectional"))
      (node (ref "JP2") (pin "2") (pinfunction "2_2") (pintype "passive"))
      (node (ref "R48") (pin "1") (pinfunction "1_1") (pintype "passive"))
      (node (ref "R95") (pin "1") (pinfunction "1_1") (pintype "passive"))
    )
    (net (code "188") (name "V+") (class "Default")
      (node (ref "C49") (pin "2") (pinfunction "2_2") (pintype "passive"))
      (node (ref "C50") (pin "1") (pinfunction "1_1") (pintype "passive"))
      (node (ref "C51") (pin "2") (pinfunction "2_2") (pintype "passive"))
      (node (ref "C52") (pin "2") (pinfunction "2_2") (pintype "passive"))
      (node (ref "C53") (pin "2") (pinfunction "2_2") (pintype "passive"))
      (node (ref "C67") (pin "1") (pinfunction "1_1") (pintype "passive"))
      (node (ref "C70") (pin "1") (pinfunction "1_1") (pintype "passive"))
      (node (ref "C72") (pin "2") (pinfunction "2_2") (pintype "passive"))
      (node (ref "C74") (pin "1") (pinfunction "1_1") (pintype "passive"))
      (node (ref "C84") (pin "1") (pinfunction "1_1") (pintype "passive"))
      (node (ref "C85") (pin "2") (pinfunction "2_2") (pintype "passive"))
      (node (ref "C88") (pin "2") (pinfunction "2_2") (pintype "passive"))
      (node (ref "FB1") (pin "P$2") (pinfunction "2_P$2") (pintype "passive"))
      (node (ref "IC10") (pin "8") (pinfunction "V+_8") (pintype "power_in"))
      (node (ref "IC11") (pin "7") (pinfunction "V+_7") (pintype "power_in"))
      (node (ref "IC14") (pin "2") (pinfunction "VIN_2") (pintype "passive"))
      (node (ref "IC16") (pin "1") (pinfunction "VDD_1") (pintype "power_in"))
      (node (ref "IC17") (pin "5") (pinfunction "VDD_5") (pintype "power_in"))
      (node (ref "IC19") (pin "8") (pinfunction "V+_8") (pintype "power_in"))
      (node (ref "IC20") (pin "1") (pinfunction "+VCC_1") (pintype "passive"))
      (node (ref "IC20") (pin "5") (pinfunction "~{LE}_5") (pintype "input"))
      (node (ref "IC9") (pin "8") (pinfunction "V+_8") (pintype "power_in"))
      (node (ref "R40") (pin "2") (pinfunction "2_2") (pintype "passive"))
      (node (ref "R82") (pin "1") (pinfunction "1_1") (pintype "passive"))
    )
    (net (code "189") (name "V-") (class "Default")
      (node (ref "C54") (pin "2") (pinfunction "2_2") (pintype "passive"))
      (node (ref "C56") (pin "2") (pinfunction "2_2") (pintype "passive"))
      (node (ref "C57") (pin "1") (pinfunction "1_1") (pintype "passive"))
      (node (ref "C58") (pin "2") (pinfunction "2_2") (pintype "passive"))
      (node (ref "C59") (pin "2") (pinfunction "2_2") (pintype "passive"))
      (node (ref "C89") (pin "2") (pinfunction "2_2") (pintype "passive"))
      (node (ref "FB3") (pin "P$2") (pinfunction "2_P$2") (pintype "passive"))
      (node (ref "IC10") (pin "4") (pinfunction "V-_4") (pintype "power_in"))
      (node (ref "IC11") (pin "4") (pinfunction "V-_4") (pintype "power_in"))
      (node (ref "IC19") (pin "4") (pinfunction "V-_4") (pintype "power_in"))
      (node (ref "IC9") (pin "4") (pinfunction "V-_4") (pintype "power_in"))
    )
    (net (code "190") (name "unconnected-(IC1-PGOOD-Pad7)") (class "Default")
      (node (ref "IC1") (pin "7") (pinfunction "PGOOD_7") (pintype "output"))
    )
    (net (code "191") (name "unconnected-(IC12A-~{Q}-Pad3)") (class "Default")
      (node (ref "IC12") (pin "3") (pinfunction "~{Q}_3") (pintype "output"))
    )
    (net (code "192") (name "unconnected-(IC13-GPB5-Pad6)") (class "Default")
      (node (ref "IC13") (pin "6") (pinfunction "GPB5_6") (pintype "bidirectional"))
    )
    (net (code "193") (name "unconnected-(IC13-INTB-Pad19)") (class "Default")
      (node (ref "IC13") (pin "19") (pinfunction "INTB_19") (pintype "output"))
    )
    (net (code "194") (name "unconnected-(IC14-TEMP-Pad3)") (class "Default")
      (node (ref "IC14") (pin "3") (pinfunction "TEMP_3") (pintype "input"))
    )
    (net (code "195") (name "~{ADC_DRDY}") (class "Default")
      (node (ref "IC13") (pin "25") (pinfunction "GPA4_25") (pintype "bidirectional"))
      (node (ref "IC18") (pin "14") (pinfunction "~{DRDY}_14") (pintype "output"))
    )
    (net (code "196") (name "~{DP_DRIVE}") (class "Default")
      (node (ref "D9") (pin "A") (pinfunction "A_A") (pintype "passive"))
      (node (ref "Q7") (pin "E") (pinfunction "E_E") (pintype "passive"))
      (node (ref "R74") (pin "1") (pinfunction "1_1") (pintype "passive"))
    )
    (net (code "197") (name "~{OVP_FAULT}") (class "Default")
      (node (ref "C64") (pin "1") (pinfunction "1_1") (pintype "passive"))
      (node (ref "D15") (pin "C") (pinfunction "C_C") (pintype "passive"))
      (node (ref "IC13") (pin "26") (pinfunction "GPA5_26") (pintype "bidirectional"))
      (node (ref "Q17") (pin "3") (pinfunction "D_3") (pintype "passive"))
      (node (ref "R70") (pin "2") (pinfunction "2_2") (pintype "passive"))
    )
    (net (code "198") (name "~{RESET}") (class "Default")
      (node (ref "IC7") (pin "12") (pinfunction "B3_12") (pintype "output"))
      (node (ref "JP1") (pin "1") (pinfunction "1_1") (pintype "passive"))
    )
    (net (code "199") (name "~{SET_DP}") (class "Default")
      (node (ref "IC13") (pin "1") (pinfunction "GPB0_1") (pintype "bidirectional"))
      (node (ref "Q12") (pin "1") (pinfunction "G_1") (pintype "passive"))
      (node (ref "R72") (pin "2") (pinfunction "2_2") (pintype "passive"))
    )
  )
)
